# STM32F407_CORE.net
KiCad netlist of a schematic drawn in Altium Designer
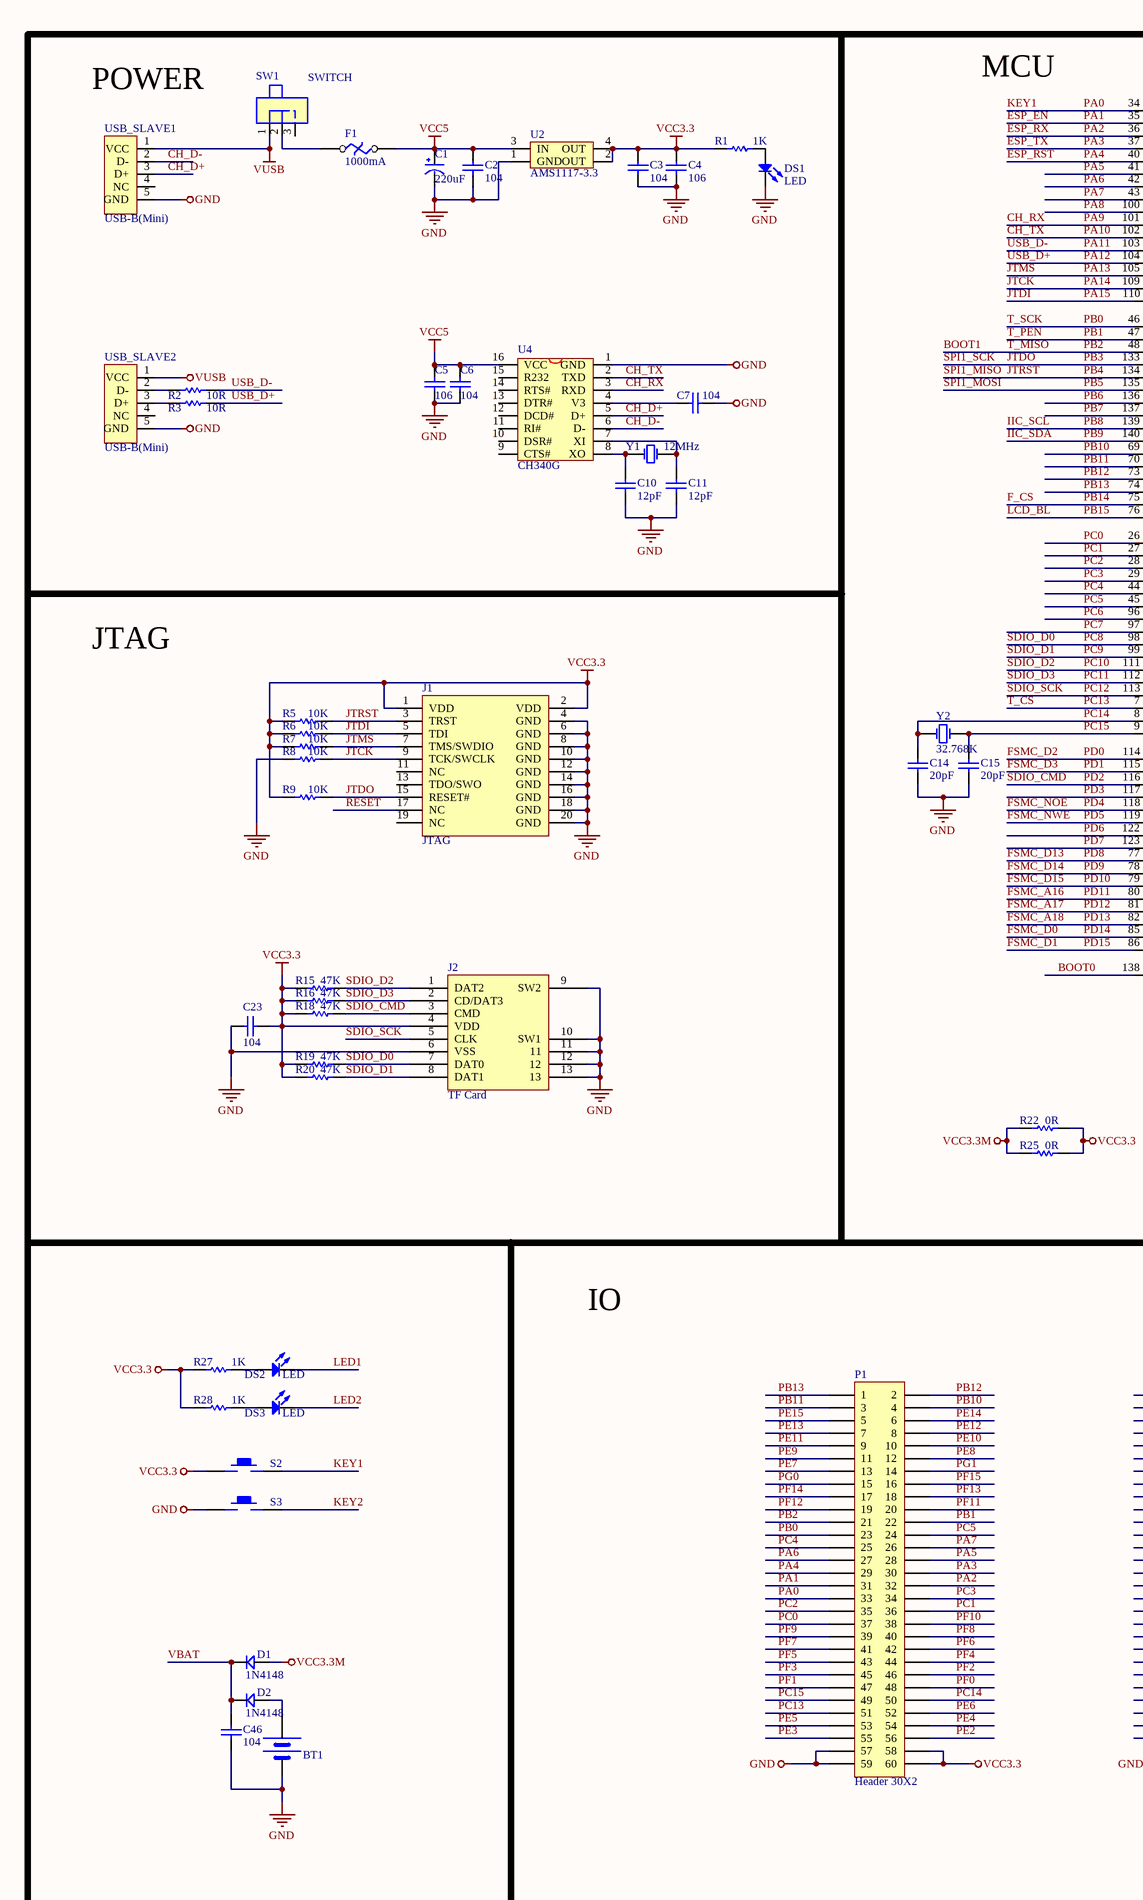
[diagram p0: STM32F407_CORE.SchDoc, left]
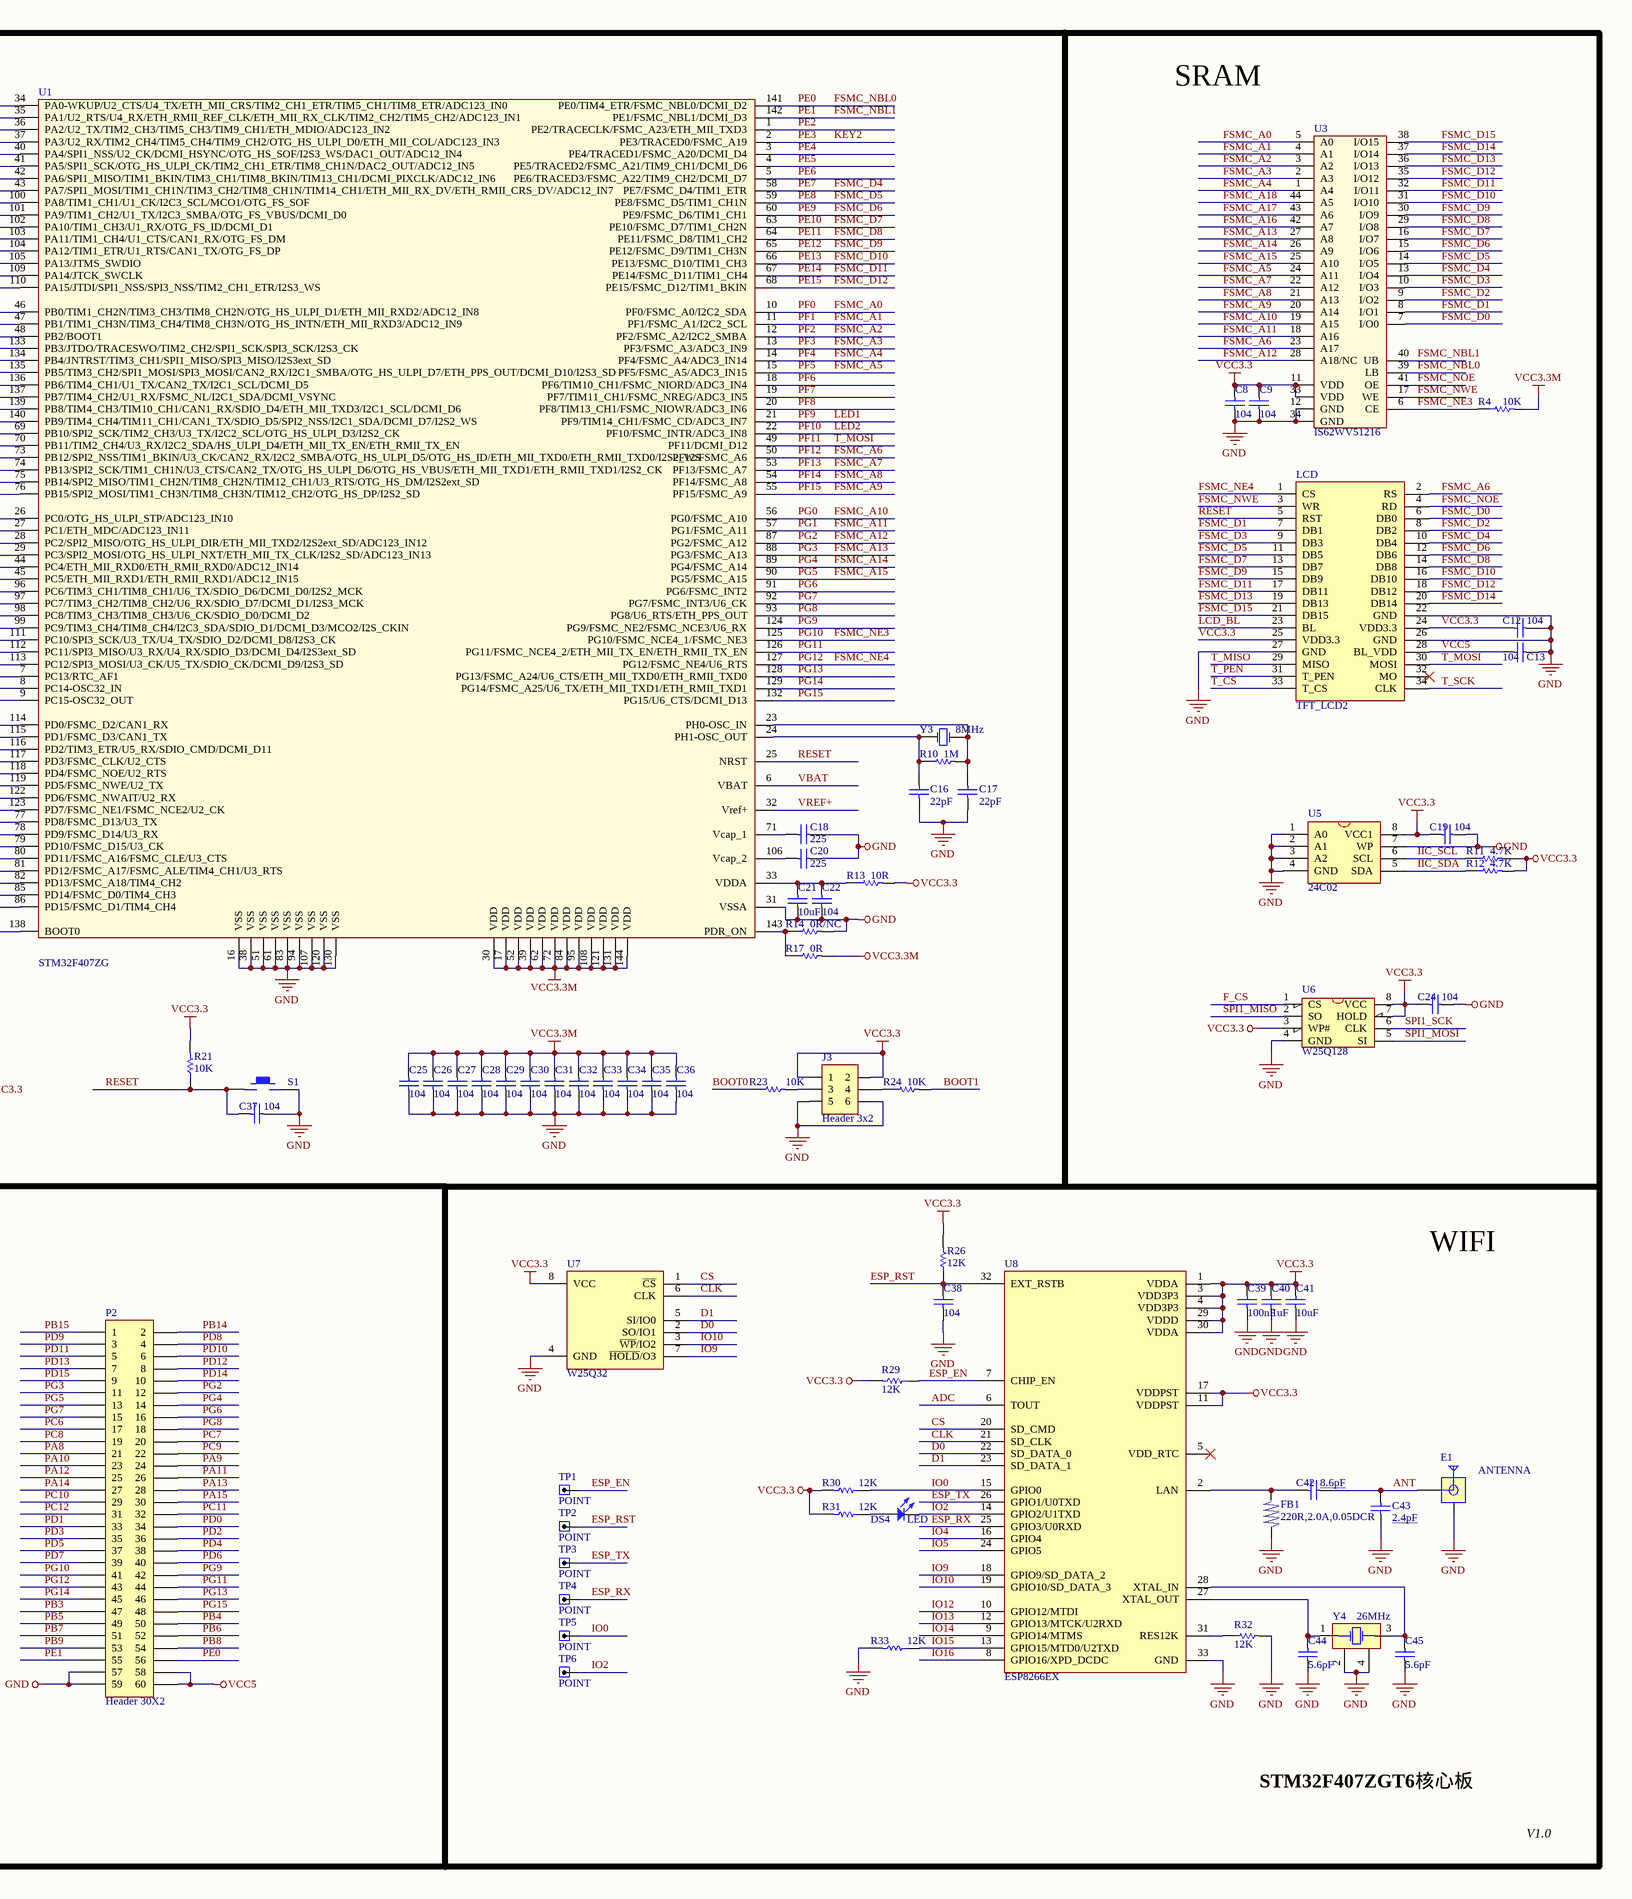
[diagram p1: STM32F407_CORE.SchDoc, right]

(export (version "E")
  (design (tool "Eeschema 10.0.6"))
  (components
    (comp (ref "BT1")
      (value "BATTERY")
      (footprint "SBAT-1220")
      (description "电池座")
      (libsource (lib "Devices") (part "BATTERY"))
    )
    (comp (ref "C1")
      (value "220uF")
      (footprint "TAJ-B")
      (description "极性电容")
      (libsource (lib "Devices") (part "C Pol"))
    )
    (comp (ref "C2")
      (value "104")
      (footprint "C0603")
      (description "电容")
      (fields (field (name "PUBLISHER") "Altium Limited"))
      (libsource (lib "Devices") (part "C"))
    )
    (comp (ref "C3")
      (value "104")
      (footprint "C0603")
      (description "电容")
      (fields (field (name "PUBLISHER") "Altium Limited"))
      (libsource (lib "Devices") (part "C"))
    )
    (comp (ref "C4")
      (value "106")
      (footprint "C0603")
      (description "电容")
      (fields (field (name "PUBLISHER") "Altium Limited"))
      (libsource (lib "Devices") (part "C"))
    )
    (comp (ref "C5")
      (value "106")
      (footprint "C0603")
      (description "电容")
      (fields (field (name "PUBLISHER") "Altium Limited"))
      (libsource (lib "Devices") (part "C"))
    )
    (comp (ref "C6")
      (value "104")
      (footprint "C0603")
      (description "电容")
      (fields (field (name "PUBLISHER") "Altium Limited"))
      (libsource (lib "Devices") (part "C"))
    )
    (comp (ref "C7")
      (value "104")
      (footprint "C0603")
      (description "电容")
      (fields (field (name "PUBLISHER") "Altium Limited"))
      (libsource (lib "Devices") (part "C"))
    )
    (comp (ref "C8")
      (value "104")
      (footprint "C0603")
      (description "电容")
      (fields (field (name "PUBLISHER") "Altium Limited"))
      (libsource (lib "Devices") (part "C"))
    )
    (comp (ref "C9")
      (value "104")
      (footprint "C0603")
      (description "电容")
      (fields (field (name "PUBLISHER") "Altium Limited"))
      (libsource (lib "Devices") (part "C"))
    )
    (comp (ref "C10")
      (value "12pF")
      (footprint "C0603")
      (description "电容")
      (fields (field (name "PUBLISHER") "Altium Limited"))
      (libsource (lib "Devices") (part "C"))
    )
    (comp (ref "C11")
      (value "12pF")
      (footprint "C0603")
      (description "电容")
      (fields (field (name "PUBLISHER") "Altium Limited"))
      (libsource (lib "Devices") (part "C"))
    )
    (comp (ref "C12")
      (value "104")
      (footprint "C0603")
      (description "电容")
      (fields (field (name "PUBLISHER") "Altium Limited"))
      (libsource (lib "Devices") (part "C"))
    )
    (comp (ref "C13")
      (value "104")
      (footprint "C0603")
      (description "电容")
      (fields (field (name "PUBLISHER") "Altium Limited"))
      (libsource (lib "Devices") (part "C"))
    )
    (comp (ref "C14")
      (value "20pF")
      (footprint "C0603")
      (description "电容")
      (fields (field (name "PUBLISHER") "Altium Limited"))
      (libsource (lib "Devices") (part "C"))
    )
    (comp (ref "C15")
      (value "20pF")
      (footprint "C0603")
      (description "电容")
      (fields (field (name "PUBLISHER") "Altium Limited"))
      (libsource (lib "Devices") (part "C"))
    )
    (comp (ref "C16")
      (value "22pF")
      (footprint "C0603")
      (description "电容")
      (fields (field (name "PUBLISHER") "Altium Limited"))
      (libsource (lib "Devices") (part "C"))
    )
    (comp (ref "C17")
      (value "22pF")
      (footprint "C0603")
      (description "电容")
      (fields (field (name "PUBLISHER") "Altium Limited"))
      (libsource (lib "Devices") (part "C"))
    )
    (comp (ref "C18")
      (value "225")
      (footprint "C0603")
      (description "电容")
      (fields (field (name "PUBLISHER") "Altium Limited"))
      (libsource (lib "Devices") (part "C"))
    )
    (comp (ref "C19")
      (value "104")
      (footprint "C0603")
      (description "电容")
      (fields (field (name "PUBLISHER") "Altium Limited"))
      (libsource (lib "Devices") (part "C"))
    )
    (comp (ref "C20")
      (value "225")
      (footprint "C0603")
      (description "电容")
      (fields (field (name "PUBLISHER") "Altium Limited"))
      (libsource (lib "Devices") (part "C"))
    )
    (comp (ref "C21")
      (value "10uF")
      (footprint "C0603")
      (description "电容")
      (fields (field (name "PUBLISHER") "Altium Limited"))
      (libsource (lib "Devices") (part "C"))
    )
    (comp (ref "C22")
      (value "104")
      (footprint "C0603")
      (description "电容")
      (fields (field (name "PUBLISHER") "Altium Limited"))
      (libsource (lib "Devices") (part "C"))
    )
    (comp (ref "C23")
      (value "104")
      (footprint "C0603")
      (description "电容")
      (fields (field (name "PUBLISHER") "Altium Limited"))
      (libsource (lib "Devices") (part "C"))
    )
    (comp (ref "C24")
      (value "104")
      (footprint "C0603")
      (description "电容")
      (fields (field (name "PUBLISHER") "Altium Limited"))
      (libsource (lib "Devices") (part "C"))
    )
    (comp (ref "C25")
      (value "104")
      (footprint "C0603")
      (description "电容")
      (fields (field (name "PUBLISHER") "Altium Limited"))
      (libsource (lib "Devices") (part "C"))
    )
    (comp (ref "C26")
      (value "104")
      (footprint "C0603")
      (description "电容")
      (fields (field (name "PUBLISHER") "Altium Limited"))
      (libsource (lib "Devices") (part "C"))
    )
    (comp (ref "C27")
      (value "104")
      (footprint "C0603")
      (description "电容")
      (fields (field (name "PUBLISHER") "Altium Limited"))
      (libsource (lib "Devices") (part "C"))
    )
    (comp (ref "C28")
      (value "104")
      (footprint "C0603")
      (description "电容")
      (fields (field (name "PUBLISHER") "Altium Limited"))
      (libsource (lib "Devices") (part "C"))
    )
    (comp (ref "C29")
      (value "104")
      (footprint "C0603")
      (description "电容")
      (fields (field (name "PUBLISHER") "Altium Limited"))
      (libsource (lib "Devices") (part "C"))
    )
    (comp (ref "C30")
      (value "104")
      (footprint "C0603")
      (description "电容")
      (fields (field (name "PUBLISHER") "Altium Limited"))
      (libsource (lib "Devices") (part "C"))
    )
    (comp (ref "C31")
      (value "104")
      (footprint "C0603")
      (description "电容")
      (fields (field (name "PUBLISHER") "Altium Limited"))
      (libsource (lib "Devices") (part "C"))
    )
    (comp (ref "C32")
      (value "104")
      (footprint "C0603")
      (description "电容")
      (fields (field (name "PUBLISHER") "Altium Limited"))
      (libsource (lib "Devices") (part "C"))
    )
    (comp (ref "C33")
      (value "104")
      (footprint "C0603")
      (description "电容")
      (fields (field (name "PUBLISHER") "Altium Limited"))
      (libsource (lib "Devices") (part "C"))
    )
    (comp (ref "C34")
      (value "104")
      (footprint "C0603")
      (description "电容")
      (fields (field (name "PUBLISHER") "Altium Limited"))
      (libsource (lib "Devices") (part "C"))
    )
    (comp (ref "C35")
      (value "104")
      (footprint "C0603")
      (description "电容")
      (fields (field (name "PUBLISHER") "Altium Limited"))
      (libsource (lib "Devices") (part "C"))
    )
    (comp (ref "C36")
      (value "104")
      (footprint "C0603")
      (description "电容")
      (fields (field (name "PUBLISHER") "Altium Limited"))
      (libsource (lib "Devices") (part "C"))
    )
    (comp (ref "C37")
      (value "104")
      (footprint "C0603")
      (description "电容")
      (fields (field (name "PUBLISHER") "Altium Limited"))
      (libsource (lib "Devices") (part "C"))
    )
    (comp (ref "C38")
      (value "104")
      (footprint "C0603")
      (description "电容")
      (fields (field (name "PUBLISHER") "Altium Limited"))
      (libsource (lib "Devices") (part "C"))
    )
    (comp (ref "C39")
      (value "100nF")
      (footprint "C0603")
      (description "电容")
      (fields (field (name "PUBLISHER") "Altium Limited"))
      (libsource (lib "Devices") (part "C"))
    )
    (comp (ref "C40")
      (value "1uF")
      (footprint "C0603")
      (description "电容")
      (fields (field (name "PUBLISHER") "Altium Limited"))
      (libsource (lib "Devices") (part "C"))
    )
    (comp (ref "C41")
      (value "10uF")
      (footprint "C0603")
      (description "电容")
      (fields (field (name "PUBLISHER") "Altium Limited"))
      (libsource (lib "Devices") (part "C"))
    )
    (comp (ref "C42")
      (value "8.6pF")
      (footprint "C0603")
      (description "电容")
      (fields (field (name "PUBLISHER") "Altium Limited"))
      (libsource (lib "Devices") (part "C"))
    )
    (comp (ref "C43")
      (value "2.4pF")
      (footprint "C0603")
      (description "电容")
      (fields (field (name "PUBLISHER") "Altium Limited"))
      (libsource (lib "Devices") (part "C"))
    )
    (comp (ref "C44")
      (value "5.6pF")
      (footprint "C0603")
      (description "电容")
      (fields (field (name "PUBLISHER") "Altium Limited"))
      (libsource (lib "Devices") (part "C"))
    )
    (comp (ref "C45")
      (value "5.6pF")
      (footprint "C0603")
      (description "电容")
      (fields (field (name "PUBLISHER") "Altium Limited"))
      (libsource (lib "Devices") (part "C"))
    )
    (comp (ref "C46")
      (value "104")
      (footprint "C0603")
      (description "电容")
      (fields (field (name "PUBLISHER") "Altium Limited"))
      (libsource (lib "Devices") (part "C"))
    )
    (comp (ref "D1")
      (value "1N4148")
      (footprint "D1206")
      (description "通用二极管")
      (libsource (lib "Devices") (part "D"))
    )
    (comp (ref "D2")
      (value "1N4148")
      (footprint "D1206")
      (description "通用二极管")
      (libsource (lib "Devices") (part "D"))
    )
    (comp (ref "DS1")
      (value "LED")
      (footprint "LED0603")
      (description "Typical RED, GREEN, YELLOW, AMBER GaAs LED")
      (fields (field (name "PUBLISHER") "Altium Limited"))
      (libsource (lib "Devices") (part "LED"))
    )
    (comp (ref "DS2")
      (value "LED")
      (footprint "LED0603")
      (description "Typical RED, GREEN, YELLOW, AMBER GaAs LED")
      (fields (field (name "PUBLISHER") "Altium Limited"))
      (libsource (lib "Devices") (part "LED"))
    )
    (comp (ref "DS3")
      (value "LED")
      (footprint "LED0603")
      (description "Typical RED, GREEN, YELLOW, AMBER GaAs LED")
      (fields (field (name "PUBLISHER") "Altium Limited"))
      (libsource (lib "Devices") (part "LED"))
    )
    (comp (ref "DS4")
      (value "LED")
      (footprint "LED0603")
      (description "Typical RED, GREEN, YELLOW, AMBER GaAs LED")
      (fields (field (name "PUBLISHER") "Altium Limited"))
      (libsource (lib "Devices") (part "LED"))
    )
    (comp (ref "E1") (value "ANTENNA") (footprint "ANT2.4G") (libsource (lib "Devices") (part "ANTENNA")))
    (comp (ref "F1")
      (value "1000mA")
      (footprint "F0805")
      (description "熔断开关")
      (libsource (lib "Devices") (part "F"))
    )
    (comp (ref "FB1")
      (value "220R,2.0A,0.05DCR")
      (footprint "L0805")
      (description "磁珠")
      (libsource (lib "Devices") (part "L-Beads"))
    )
    (comp (ref "J1") (value "JTAG") (footprint "DC3-20P-W") (libsource (lib "Connectors") (part "JTAG")))
    (comp (ref "J2") (value "TF Card") (footprint "TF-Card") (libsource (lib "Devices") (part "TF Card")))
    (comp (ref "J3")
      (value "Header 3x2")
      (footprint "HDR2X3")
      (description "Header, 6-Pin")
      (fields (field (name "PUBLISHER") "Altium Limited"))
      (libsource (lib "Connectors") (part "Header 3x2"))
    )
    (comp (ref "LCD")
      (value "TFT_LCD2")
      (footprint "TFT-HDR2X17")
      (libsource (lib "Connectors") (part "TFT_LCD2"))
    )
    (comp (ref "P1")
      (value "Header 30X2")
      (footprint "HDR2X30")
      (description "Header, 60-Pin, Dual row")
      (fields (field (name "PUBLISHER") "Altium Limited"))
      (libsource (lib "Connectors") (part "Header 30X2"))
    )
    (comp (ref "P2")
      (value "Header 30X2")
      (footprint "HDR2X30")
      (description "Header, 60-Pin, Dual row")
      (fields (field (name "PUBLISHER") "Altium Limited"))
      (libsource (lib "Connectors") (part "Header 30X2"))
    )
    (comp (ref "R1")
      (value "1K")
      (footprint "R0603")
      (description "电阻")
      (fields (field (name "PUBLISHER") "Altium Limited"))
      (libsource (lib "Devices") (part "RES0603"))
    )
    (comp (ref "R2")
      (value "10R")
      (footprint "R0603")
      (description "电阻")
      (fields (field (name "PUBLISHER") "Altium Limited"))
      (libsource (lib "Devices") (part "RES0603"))
    )
    (comp (ref "R3")
      (value "10R")
      (footprint "R0603")
      (description "电阻")
      (fields (field (name "PUBLISHER") "Altium Limited"))
      (libsource (lib "Devices") (part "RES0603"))
    )
    (comp (ref "R4")
      (value "10K")
      (footprint "R0603")
      (description "电阻")
      (fields (field (name "PUBLISHER") "Altium Limited"))
      (libsource (lib "Devices") (part "RES0603"))
    )
    (comp (ref "R5")
      (value "10K")
      (footprint "R0603")
      (description "电阻")
      (fields (field (name "PUBLISHER") "Altium Limited"))
      (libsource (lib "Devices") (part "RES0603"))
    )
    (comp (ref "R6")
      (value "10K")
      (footprint "R0603")
      (description "电阻")
      (fields (field (name "PUBLISHER") "Altium Limited"))
      (libsource (lib "Devices") (part "RES0603"))
    )
    (comp (ref "R7")
      (value "10K")
      (footprint "R0603")
      (description "电阻")
      (fields (field (name "PUBLISHER") "Altium Limited"))
      (libsource (lib "Devices") (part "RES0603"))
    )
    (comp (ref "R8")
      (value "10K")
      (footprint "R0603")
      (description "电阻")
      (fields (field (name "PUBLISHER") "Altium Limited"))
      (libsource (lib "Devices") (part "RES0603"))
    )
    (comp (ref "R9")
      (value "10K")
      (footprint "R0603")
      (description "电阻")
      (fields (field (name "PUBLISHER") "Altium Limited"))
      (libsource (lib "Devices") (part "RES0603"))
    )
    (comp (ref "R10")
      (value "1M")
      (footprint "R0603")
      (description "电阻")
      (fields (field (name "PUBLISHER") "Altium Limited"))
      (libsource (lib "Devices") (part "RES0603"))
    )
    (comp (ref "R11")
      (value "4.7K")
      (footprint "R0603")
      (description "电阻")
      (fields (field (name "PUBLISHER") "Altium Limited"))
      (libsource (lib "Devices") (part "RES0603"))
    )
    (comp (ref "R12")
      (value "4.7K")
      (footprint "R0603")
      (description "电阻")
      (fields (field (name "PUBLISHER") "Altium Limited"))
      (libsource (lib "Devices") (part "RES0603"))
    )
    (comp (ref "R13")
      (value "10R")
      (footprint "R0603")
      (description "电阻")
      (fields (field (name "PUBLISHER") "Altium Limited"))
      (libsource (lib "Devices") (part "RES0603"))
    )
    (comp (ref "R14")
      (value "0R/NC")
      (footprint "R0603")
      (description "电阻")
      (fields (field (name "PUBLISHER") "Altium Limited"))
      (libsource (lib "Devices") (part "RES0603"))
    )
    (comp (ref "R15")
      (value "47K")
      (footprint "R0603")
      (description "电阻")
      (fields (field (name "PUBLISHER") "Altium Limited"))
      (libsource (lib "Devices") (part "RES0603"))
    )
    (comp (ref "R16")
      (value "47K")
      (footprint "R0603")
      (description "电阻")
      (fields (field (name "PUBLISHER") "Altium Limited"))
      (libsource (lib "Devices") (part "RES0603"))
    )
    (comp (ref "R17")
      (value "0R")
      (footprint "R0603")
      (description "电阻")
      (fields (field (name "PUBLISHER") "Altium Limited"))
      (libsource (lib "Devices") (part "RES0603"))
    )
    (comp (ref "R18")
      (value "47K")
      (footprint "R0603")
      (description "电阻")
      (fields (field (name "PUBLISHER") "Altium Limited"))
      (libsource (lib "Devices") (part "RES0603"))
    )
    (comp (ref "R19")
      (value "47K")
      (footprint "R0603")
      (description "电阻")
      (fields (field (name "PUBLISHER") "Altium Limited"))
      (libsource (lib "Devices") (part "RES0603"))
    )
    (comp (ref "R20")
      (value "47K")
      (footprint "R0603")
      (description "电阻")
      (fields (field (name "PUBLISHER") "Altium Limited"))
      (libsource (lib "Devices") (part "RES0603"))
    )
    (comp (ref "R21")
      (value "10K")
      (footprint "R0603")
      (description "电阻")
      (fields (field (name "PUBLISHER") "Altium Limited"))
      (libsource (lib "Devices") (part "RES0603"))
    )
    (comp (ref "R22")
      (value "0R")
      (footprint "R0603")
      (description "电阻")
      (fields (field (name "PUBLISHER") "Altium Limited"))
      (libsource (lib "Devices") (part "RES0603"))
    )
    (comp (ref "R23")
      (value "10K")
      (footprint "R0603")
      (description "电阻")
      (fields (field (name "PUBLISHER") "Altium Limited"))
      (libsource (lib "Devices") (part "RES0603"))
    )
    (comp (ref "R24")
      (value "10K")
      (footprint "R0603")
      (description "电阻")
      (fields (field (name "PUBLISHER") "Altium Limited"))
      (libsource (lib "Devices") (part "RES0603"))
    )
    (comp (ref "R25")
      (value "0R")
      (footprint "R0603")
      (description "电阻")
      (fields (field (name "PUBLISHER") "Altium Limited"))
      (libsource (lib "Devices") (part "RES0603"))
    )
    (comp (ref "R26")
      (value "12K")
      (footprint "R0603")
      (description "电阻")
      (fields (field (name "PUBLISHER") "Altium Limited"))
      (libsource (lib "Devices") (part "RES0603"))
    )
    (comp (ref "R27")
      (value "1K")
      (footprint "R0603")
      (description "电阻")
      (fields (field (name "PUBLISHER") "Altium Limited"))
      (libsource (lib "Devices") (part "RES0603"))
    )
    (comp (ref "R28")
      (value "1K")
      (footprint "R0603")
      (description "电阻")
      (fields (field (name "PUBLISHER") "Altium Limited"))
      (libsource (lib "Devices") (part "RES0603"))
    )
    (comp (ref "R29")
      (value "12K")
      (footprint "R0603")
      (description "电阻")
      (fields (field (name "PUBLISHER") "Altium Limited"))
      (libsource (lib "Devices") (part "RES0603"))
    )
    (comp (ref "R30")
      (value "12K")
      (footprint "R0603")
      (description "电阻")
      (fields (field (name "PUBLISHER") "Altium Limited"))
      (libsource (lib "Devices") (part "RES0603"))
    )
    (comp (ref "R31")
      (value "12K")
      (footprint "R0603")
      (description "电阻")
      (fields (field (name "PUBLISHER") "Altium Limited"))
      (libsource (lib "Devices") (part "RES0603"))
    )
    (comp (ref "R32")
      (value "12K")
      (footprint "R0603")
      (description "电阻")
      (fields (field (name "PUBLISHER") "Altium Limited"))
      (libsource (lib "Devices") (part "RES0603"))
    )
    (comp (ref "R33")
      (value "12K")
      (footprint "R0603")
      (description "电阻")
      (fields (field (name "PUBLISHER") "Altium Limited"))
      (libsource (lib "Devices") (part "RES0603"))
    )
    (comp (ref "S1")
      (value "KEY")
      (footprint "DSW-KFC-022S-H2.5")
      (description "普通轻触按钮")
      (libsource (lib "Devices") (part "KEY"))
    )
    (comp (ref "S2")
      (value "KEY")
      (footprint "DSW-KEY-SOT-4_5x4_5")
      (description "普通轻触按钮")
      (libsource (lib "Devices") (part "KEY"))
    )
    (comp (ref "S3")
      (value "KEY")
      (footprint "DSW-KEY-SOT-4_5x4_5")
      (description "普通轻触按钮")
      (libsource (lib "Devices") (part "KEY"))
    )
    (comp (ref "SW1")
      (value "SWITCH")
      (footprint "SW-SS12D07VG4")
      (libsource (lib "Devices") (part "SWITCH"))
    )
    (comp (ref "TP1") (value "POINT") (footprint "TP12") (libsource (lib "Connectors") (part "POINT")))
    (comp (ref "TP2") (value "POINT") (footprint "TP12") (libsource (lib "Connectors") (part "POINT")))
    (comp (ref "TP3") (value "POINT") (footprint "TP12") (libsource (lib "Connectors") (part "POINT")))
    (comp (ref "TP4") (value "POINT") (footprint "TP12") (libsource (lib "Connectors") (part "POINT")))
    (comp (ref "TP5") (value "POINT") (footprint "TP12") (libsource (lib "Connectors") (part "POINT")))
    (comp (ref "TP6") (value "POINT") (footprint "TP12") (libsource (lib "Connectors") (part "POINT")))
    (comp (ref "U1") (value "STM32F407ZG") (footprint "LQFP-144") (libsource (lib "IC") (part "STM32F407ZG")))
    (comp (ref "U2")
      (value "AMS1117-3.3")
      (footprint "SOT-223")
      (description "电源转换5Vto3.3V")
      (libsource (lib "IC") (part "AMS1117"))
    )
    (comp (ref "U3") (value "IS62WV51216") (footprint "TSOP-44") (libsource (lib "IC") (part "IS61LV51216")))
    (comp (ref "U4")
      (value "CH340G")
      (footprint "SOP-16M")
      (description "USB2UART")
      (libsource (lib "IC") (part "CH340G"))
    )
    (comp (ref "U5") (value "24C02") (footprint "SOP-8") (libsource (lib "IC") (part "24C256")))
    (comp (ref "U6")
      (value "W25Q128")
      (footprint "SOIC-8")
      (description "W25X16;SST25VF016;MX25L1605")
      (libsource (lib "IC") (part "W25X16"))
    )
    (comp (ref "U7") (value "W25Q32") (footprint "SOIC-8") (libsource (lib "IC") (part "W25Q32")))
    (comp (ref "U8") (value "ESP8266EX") (footprint "QFN-32-1") (libsource (lib "IC") (part "ESP8266EX")))
    (comp (ref "USB_SLAVE1")
      (value "USB-B(Mini)")
      (footprint "USB-MicroUSB")
      (libsource (lib "Connectors") (part "USB5"))
    )
    (comp (ref "USB_SLAVE2")
      (value "USB-B(Mini)")
      (footprint "USB-MicroUSB")
      (libsource (lib "Connectors") (part "USB5"))
    )
    (comp (ref "Y1")
      (value "12MHz")
      (footprint "X-HC49-SMT")
      (description "Crystal Oscillator")
      (fields (field (name "PUBLISHER") "Altium Limited"))
      (libsource (lib "Devices") (part "XTAL"))
    )
    (comp (ref "Y2")
      (value "32.768K")
      (footprint "X-MC146")
      (description "Crystal Oscillator")
      (fields (field (name "PUBLISHER") "Altium Limited"))
      (libsource (lib "Devices") (part "XTAL"))
    )
    (comp (ref "Y3")
      (value "8MHz")
      (footprint "X-HC49-SMT")
      (description "Crystal Oscillator")
      (fields (field (name "PUBLISHER") "Altium Limited"))
      (libsource (lib "Devices") (part "XTAL"))
    )
    (comp (ref "Y4")
      (value "26MHz")
      (footprint "X-TSX-3225")
      (description "Crystal Oscillator")
      (fields (field (name "PUBLISHER") "Altium Limited"))
      (libsource (lib "Devices") (part "XTAL_1"))
    )
  )
  (nets
    (net (code "1") (name "/ADC") (class "Default")
      (node (ref "U8") (pin "6") (pinfunction "TOUT_6") (pintype "power_in"))
    )
    (net (code "2") (name "/ANT") (class "Default")
      (node (ref "C42") (pin "1") (pinfunction "1_1") (pintype "passive"))
      (node (ref "C43") (pin "1") (pinfunction "1_1") (pintype "passive"))
      (node (ref "E1") (pin "1") (pinfunction "1_1") (pintype "passive"))
    )
    (net (code "3") (name "/BOOT0") (class "Default")
      (node (ref "R23") (pin "1") (pinfunction "1_1") (pintype "passive"))
      (node (ref "U1") (pin "138") (pinfunction "BOOT0_138") (pintype "passive"))
    )
    (net (code "4") (name "/BOOT1") (class "Default")
      (node (ref "LCD") (pin "29") (pinfunction "MISO_29") (pintype "passive"))
      (node (ref "P1") (pin "21") (pinfunction "21_21") (pintype "passive"))
      (node (ref "R24") (pin "2") (pinfunction "2_2") (pintype "passive"))
      (node (ref "U1") (pin "48") (pinfunction "PB2/BOOT1_48") (pintype "passive"))
    )
    (net (code "5") (name "/CH_D+") (class "Default")
      (node (ref "U4") (pin "5") (pinfunction "D+_5") (pintype "passive"))
      (node (ref "USB_SLAVE1") (pin "3") (pinfunction "D+_3") (pintype "passive"))
    )
    (net (code "6") (name "/CH_D-") (class "Default")
      (node (ref "U4") (pin "6") (pinfunction "D-_6") (pintype "passive"))
      (node (ref "USB_SLAVE1") (pin "2") (pinfunction "D-_2") (pintype "passive"))
    )
    (net (code "7") (name "/CH_RX") (class "Default")
      (node (ref "P2") (pin "24") (pinfunction "24_24") (pintype "passive"))
      (node (ref "U1") (pin "101") (pinfunction "PA9/TIM1_CH2/U1_TX/I2C3_SMBA/OTG_FS_VBUS/DCMI_D0_101") (pintype "passive"))
      (node (ref "U4") (pin "3") (pinfunction "RXD_3") (pintype "passive"))
    )
    (net (code "8") (name "/CH_TX") (class "Default")
      (node (ref "P2") (pin "23") (pinfunction "23_23") (pintype "passive"))
      (node (ref "U1") (pin "102") (pinfunction "PA10/TIM1_CH3/U1_RX/OTG_FS_ID/DCMI_D1_102") (pintype "passive"))
      (node (ref "U4") (pin "2") (pinfunction "TXD_2") (pintype "passive"))
    )
    (net (code "9") (name "/CLK") (class "Default")
      (node (ref "U7") (pin "6") (pinfunction "CLK_6") (pintype "power_in"))
      (node (ref "U8") (pin "21") (pinfunction "SD_CLK_21") (pintype "power_in"))
    )
    (net (code "10") (name "/CS") (class "Default")
      (node (ref "U7") (pin "1") (pinfunction "~{CS}_1") (pintype "power_in"))
      (node (ref "U8") (pin "20") (pinfunction "SD_CMD_20") (pintype "power_in"))
    )
    (net (code "11") (name "/D0") (class "Default")
      (node (ref "U7") (pin "2") (pinfunction "SO/IO1_2") (pintype "power_in"))
      (node (ref "U8") (pin "22") (pinfunction "SD_DATA_0_22") (pintype "power_in"))
    )
    (net (code "12") (name "/D1") (class "Default")
      (node (ref "U7") (pin "5") (pinfunction "SI/IO0_5") (pintype "power_in"))
      (node (ref "U8") (pin "23") (pinfunction "SD_DATA_1_23") (pintype "power_in"))
    )
    (net (code "13") (name "/ESP_EN") (class "Default")
      (node (ref "P1") (pin "31") (pinfunction "31_31") (pintype "passive"))
      (node (ref "R29") (pin "1") (pinfunction "1_1") (pintype "passive"))
      (node (ref "TP1") (pin "1") (pinfunction "1_1") (pintype "passive"))
      (node (ref "U1") (pin "35") (pinfunction "PA1/U2_RTS/U4_RX/ETH_RMII_REF_CLK/ETH_MII_RX_CLK/TIM2_CH2/TIM5_CH2/ADC123_IN1_35") (pintype "passive"))
      (node (ref "U8") (pin "7") (pinfunction "CHIP_EN_7") (pintype "power_in"))
    )
    (net (code "14") (name "/ESP_RST") (class "Default")
      (node (ref "C38") (pin "2") (pinfunction "2_2") (pintype "passive"))
      (node (ref "P1") (pin "29") (pinfunction "29_29") (pintype "passive"))
      (node (ref "R26") (pin "1") (pinfunction "1_1") (pintype "passive"))
      (node (ref "TP2") (pin "1") (pinfunction "1_1") (pintype "passive"))
      (node (ref "U1") (pin "40") (pinfunction "PA4/SPI1_NSS/U2_CK/DCMI_HSYNC/OTG_HS_SOF/I2S3_WS/DAC1_OUT/ADC12_IN4_40") (pintype "passive"))
      (node (ref "U8") (pin "32") (pinfunction "EXT_RSTB_32") (pintype "power_in"))
    )
    (net (code "15") (name "/ESP_RX") (class "Default")
      (node (ref "P1") (pin "32") (pinfunction "32_32") (pintype "passive"))
      (node (ref "TP4") (pin "1") (pinfunction "1_1") (pintype "passive"))
      (node (ref "U1") (pin "36") (pinfunction "PA2/U2_TX/TIM2_CH3/TIM5_CH3/TIM9_CH1/ETH_MDIO/ADC123_IN2_36") (pintype "passive"))
      (node (ref "U8") (pin "25") (pinfunction "GPIO3/U0RXD_25") (pintype "power_in"))
    )
    (net (code "16") (name "/ESP_TX") (class "Default")
      (node (ref "P1") (pin "30") (pinfunction "30_30") (pintype "passive"))
      (node (ref "TP3") (pin "1") (pinfunction "1_1") (pintype "passive"))
      (node (ref "U1") (pin "37") (pinfunction "PA3/U2_RX/TIM2_CH4/TIM5_CH4/TIM9_CH2/OTG_HS_ULPI_D0/ETH_MII_COL/ADC123_IN3_37") (pintype "passive"))
      (node (ref "U8") (pin "26") (pinfunction "GPIO1/U0TXD_26") (pintype "power_in"))
    )
    (net (code "17") (name "/FSMC_A0") (class "Default")
      (node (ref "P1") (pin "48") (pinfunction "48_48") (pintype "passive"))
      (node (ref "U1") (pin "10") (pinfunction "PF0/FSMC_A0/I2C2_SDA_10") (pintype "passive"))
      (node (ref "U3") (pin "5") (pinfunction "A0_5") (pintype "passive"))
    )
    (net (code "18") (name "/FSMC_A1") (class "Default")
      (node (ref "P1") (pin "47") (pinfunction "47_47") (pintype "passive"))
      (node (ref "U1") (pin "11") (pinfunction "PF1/FSMC_A1/I2C2_SCL_11") (pintype "passive"))
      (node (ref "U3") (pin "4") (pinfunction "A1_4") (pintype "passive"))
    )
    (net (code "19") (name "/FSMC_A2") (class "Default")
      (node (ref "P1") (pin "46") (pinfunction "46_46") (pintype "passive"))
      (node (ref "U1") (pin "12") (pinfunction "PF2/FSMC_A2/I2C2_SMBA_12") (pintype "passive"))
      (node (ref "U3") (pin "3") (pinfunction "A2_3") (pintype "passive"))
    )
    (net (code "20") (name "/FSMC_A3") (class "Default")
      (node (ref "P1") (pin "45") (pinfunction "45_45") (pintype "passive"))
      (node (ref "U1") (pin "13") (pinfunction "PF3/FSMC_A3/ADC3_IN9_13") (pintype "passive"))
      (node (ref "U3") (pin "2") (pinfunction "A3_2") (pintype "passive"))
    )
    (net (code "21") (name "/FSMC_A4") (class "Default")
      (node (ref "P1") (pin "44") (pinfunction "44_44") (pintype "passive"))
      (node (ref "U1") (pin "14") (pinfunction "PF4/FSMC_A4/ADC3_IN14_14") (pintype "passive"))
      (node (ref "U3") (pin "1") (pinfunction "A4_1") (pintype "passive"))
    )
    (net (code "22") (name "/FSMC_A5") (class "Default")
      (node (ref "P1") (pin "43") (pinfunction "43_43") (pintype "passive"))
      (node (ref "U1") (pin "15") (pinfunction "PF5/FSMC_A5/ADC3_IN15_15") (pintype "passive"))
      (node (ref "U3") (pin "24") (pinfunction "A11_24") (pintype "passive"))
    )
    (net (code "23") (name "/FSMC_A6") (class "Default")
      (node (ref "LCD") (pin "2") (pinfunction "RS_2") (pintype "passive"))
      (node (ref "P1") (pin "19") (pinfunction "19_19") (pintype "passive"))
      (node (ref "U1") (pin "50") (pinfunction "PF12/FSMC_A6_50") (pintype "passive"))
      (node (ref "U3") (pin "23") (pinfunction "A17_23") (pintype "passive"))
    )
    (net (code "24") (name "/FSMC_A7") (class "Default")
      (node (ref "P1") (pin "18") (pinfunction "18_18") (pintype "passive"))
      (node (ref "U1") (pin "53") (pinfunction "PF13/FSMC_A7_53") (pintype "passive"))
      (node (ref "U3") (pin "22") (pinfunction "A12_22") (pintype "passive"))
    )
    (net (code "25") (name "/FSMC_A8") (class "Default")
      (node (ref "P1") (pin "17") (pinfunction "17_17") (pintype "passive"))
      (node (ref "U1") (pin "54") (pinfunction "PF14/FSMC_A8_54") (pintype "passive"))
      (node (ref "U3") (pin "21") (pinfunction "A13_21") (pintype "passive"))
    )
    (net (code "26") (name "/FSMC_A9") (class "Default")
      (node (ref "P1") (pin "16") (pinfunction "16_16") (pintype "passive"))
      (node (ref "U1") (pin "55") (pinfunction "PF15/FSMC_A9_55") (pintype "passive"))
      (node (ref "U3") (pin "20") (pinfunction "A14_20") (pintype "passive"))
    )
    (net (code "27") (name "/FSMC_A10") (class "Default")
      (node (ref "P1") (pin "15") (pinfunction "15_15") (pintype "passive"))
      (node (ref "U1") (pin "56") (pinfunction "PG0/FSMC_A10_56") (pintype "passive"))
      (node (ref "U3") (pin "19") (pinfunction "A15_19") (pintype "passive"))
    )
    (net (code "28") (name "/FSMC_A11") (class "Default")
      (node (ref "P1") (pin "14") (pinfunction "14_14") (pintype "passive"))
      (node (ref "U1") (pin "57") (pinfunction "PG1/FSMC_A11_57") (pintype "passive"))
      (node (ref "U3") (pin "18") (pinfunction "A16_18") (pintype "passive"))
    )
    (net (code "29") (name "/FSMC_A12") (class "Default")
      (node (ref "P2") (pin "12") (pinfunction "12_12") (pintype "passive"))
      (node (ref "U1") (pin "87") (pinfunction "PG2/FSMC_A12_87") (pintype "passive"))
      (node (ref "U3") (pin "28") (pinfunction "A18/NC_28") (pintype "passive"))
    )
    (net (code "30") (name "/FSMC_A13") (class "Default")
      (node (ref "P2") (pin "11") (pinfunction "11_11") (pintype "passive"))
      (node (ref "U1") (pin "88") (pinfunction "PG3/FSMC_A13_88") (pintype "passive"))
      (node (ref "U3") (pin "27") (pinfunction "A8_27") (pintype "passive"))
    )
    (net (code "31") (name "/FSMC_A14") (class "Default")
      (node (ref "P2") (pin "14") (pinfunction "14_14") (pintype "passive"))
      (node (ref "U1") (pin "89") (pinfunction "PG4/FSMC_A14_89") (pintype "passive"))
      (node (ref "U3") (pin "26") (pinfunction "A9_26") (pintype "passive"))
    )
    (net (code "32") (name "/FSMC_A15") (class "Default")
      (node (ref "P2") (pin "13") (pinfunction "13_13") (pintype "passive"))
      (node (ref "U1") (pin "90") (pinfunction "PG5/FSMC_A15_90") (pintype "passive"))
      (node (ref "U3") (pin "25") (pinfunction "A10_25") (pintype "passive"))
    )
    (net (code "33") (name "/FSMC_A16") (class "Default")
      (node (ref "P2") (pin "5") (pinfunction "5_5") (pintype "passive"))
      (node (ref "U1") (pin "80") (pinfunction "PD11/FSMC_A16/FSMC_CLE/U3_CTS_80") (pintype "passive"))
      (node (ref "U3") (pin "42") (pinfunction "A7_42") (pintype "passive"))
    )
    (net (code "34") (name "/FSMC_A17") (class "Default")
      (node (ref "P2") (pin "8") (pinfunction "8_8") (pintype "passive"))
      (node (ref "U1") (pin "81") (pinfunction "PD12/FSMC_A17/FSMC_ALE/TIM4_CH1/U3_RTS_81") (pintype "passive"))
      (node (ref "U3") (pin "43") (pinfunction "A6_43") (pintype "passive"))
    )
    (net (code "35") (name "/FSMC_A18") (class "Default")
      (node (ref "P2") (pin "7") (pinfunction "7_7") (pintype "passive"))
      (node (ref "U1") (pin "82") (pinfunction "PD13/FSMC_A18/TIM4_CH2_82") (pintype "passive"))
      (node (ref "U3") (pin "44") (pinfunction "A5_44") (pintype "passive"))
    )
    (net (code "36") (name "/FSMC_D0") (class "Default")
      (node (ref "LCD") (pin "6") (pinfunction "DB0_6") (pintype "passive"))
      (node (ref "P2") (pin "10") (pinfunction "10_10") (pintype "passive"))
      (node (ref "U1") (pin "85") (pinfunction "PD14/FSMC_D0/TIM4_CH3_85") (pintype "passive"))
      (node (ref "U3") (pin "7") (pinfunction "I/O0_7") (pintype "passive"))
    )
    (net (code "37") (name "/FSMC_D1") (class "Default")
      (node (ref "LCD") (pin "7") (pinfunction "DB1_7") (pintype "passive"))
      (node (ref "P2") (pin "9") (pinfunction "9_9") (pintype "passive"))
      (node (ref "U1") (pin "86") (pinfunction "PD15/FSMC_D1/TIM4_CH4_86") (pintype "passive"))
      (node (ref "U3") (pin "8") (pinfunction "I/O1_8") (pintype "passive"))
    )
    (net (code "38") (name "/FSMC_D2") (class "Default")
      (node (ref "LCD") (pin "8") (pinfunction "DB2_8") (pintype "passive"))
      (node (ref "P2") (pin "34") (pinfunction "34_34") (pintype "passive"))
      (node (ref "U1") (pin "114") (pinfunction "PD0/FSMC_D2/CAN1_RX_114") (pintype "passive"))
      (node (ref "U3") (pin "9") (pinfunction "I/O2_9") (pintype "passive"))
    )
    (net (code "39") (name "/FSMC_D3") (class "Default")
      (node (ref "LCD") (pin "9") (pinfunction "DB3_9") (pintype "passive"))
      (node (ref "P2") (pin "33") (pinfunction "33_33") (pintype "passive"))
      (node (ref "U1") (pin "115") (pinfunction "PD1/FSMC_D3/CAN1_TX_115") (pintype "passive"))
      (node (ref "U3") (pin "10") (pinfunction "I/O3_10") (pintype "passive"))
    )
    (net (code "40") (name "/FSMC_D4") (class "Default")
      (node (ref "LCD") (pin "10") (pinfunction "DB4_10") (pintype "passive"))
      (node (ref "P1") (pin "13") (pinfunction "13_13") (pintype "passive"))
      (node (ref "U1") (pin "58") (pinfunction "PE7/FSMC_D4/TIM1_ETR_58") (pintype "passive"))
      (node (ref "U3") (pin "13") (pinfunction "I/O4_13") (pintype "passive"))
    )
    (net (code "41") (name "/FSMC_D5") (class "Default")
      (node (ref "LCD") (pin "11") (pinfunction "DB5_11") (pintype "passive"))
      (node (ref "P1") (pin "12") (pinfunction "12_12") (pintype "passive"))
      (node (ref "U1") (pin "59") (pinfunction "PE8/FSMC_D5/TIM1_CH1N_59") (pintype "passive"))
      (node (ref "U3") (pin "14") (pinfunction "I/O5_14") (pintype "passive"))
    )
    (net (code "42") (name "/FSMC_D6") (class "Default")
      (node (ref "LCD") (pin "12") (pinfunction "DB6_12") (pintype "passive"))
      (node (ref "P1") (pin "11") (pinfunction "11_11") (pintype "passive"))
      (node (ref "U1") (pin "60") (pinfunction "PE9/FSMC_D6/TIM1_CH1_60") (pintype "passive"))
      (node (ref "U3") (pin "15") (pinfunction "I/O6_15") (pintype "passive"))
    )
    (net (code "43") (name "/FSMC_D7") (class "Default")
      (node (ref "LCD") (pin "13") (pinfunction "DB7_13") (pintype "passive"))
      (node (ref "P1") (pin "10") (pinfunction "10_10") (pintype "passive"))
      (node (ref "U1") (pin "63") (pinfunction "PE10/FSMC_D7/TIM1_CH2N_63") (pintype "passive"))
      (node (ref "U3") (pin "16") (pinfunction "I/O7_16") (pintype "passive"))
    )
    (net (code "44") (name "/FSMC_D8") (class "Default")
      (node (ref "LCD") (pin "14") (pinfunction "DB8_14") (pintype "passive"))
      (node (ref "P1") (pin "9") (pinfunction "9_9") (pintype "passive"))
      (node (ref "U1") (pin "64") (pinfunction "PE11/FSMC_D8/TIM1_CH2_64") (pintype "passive"))
      (node (ref "U3") (pin "29") (pinfunction "I/O8_29") (pintype "passive"))
    )
    (net (code "45") (name "/FSMC_D9") (class "Default")
      (node (ref "LCD") (pin "15") (pinfunction "DB9_15") (pintype "passive"))
      (node (ref "P1") (pin "8") (pinfunction "8_8") (pintype "passive"))
      (node (ref "U1") (pin "65") (pinfunction "PE12/FSMC_D9/TIM1_CH3N_65") (pintype "passive"))
      (node (ref "U3") (pin "30") (pinfunction "I/O9_30") (pintype "passive"))
    )
    (net (code "46") (name "/FSMC_D10") (class "Default")
      (node (ref "LCD") (pin "16") (pinfunction "DB10_16") (pintype "passive"))
      (node (ref "P1") (pin "7") (pinfunction "7_7") (pintype "passive"))
      (node (ref "U1") (pin "66") (pinfunction "PE13/FSMC_D10/TIM1_CH3_66") (pintype "passive"))
      (node (ref "U3") (pin "31") (pinfunction "I/O10_31") (pintype "passive"))
    )
    (net (code "47") (name "/FSMC_D11") (class "Default")
      (node (ref "LCD") (pin "17") (pinfunction "DB11_17") (pintype "passive"))
      (node (ref "P1") (pin "6") (pinfunction "6_6") (pintype "passive"))
      (node (ref "U1") (pin "67") (pinfunction "PE14/FSMC_D11/TIM1_CH4_67") (pintype "passive"))
      (node (ref "U3") (pin "32") (pinfunction "I/O11_32") (pintype "passive"))
    )
    (net (code "48") (name "/FSMC_D12") (class "Default")
      (node (ref "LCD") (pin "18") (pinfunction "DB12_18") (pintype "passive"))
      (node (ref "P1") (pin "5") (pinfunction "5_5") (pintype "passive"))
      (node (ref "U1") (pin "68") (pinfunction "PE15/FSMC_D12/TIM1_BKIN_68") (pintype "passive"))
      (node (ref "U3") (pin "35") (pinfunction "I/O12_35") (pintype "passive"))
    )
    (net (code "49") (name "/FSMC_D13") (class "Default")
      (node (ref "LCD") (pin "19") (pinfunction "DB13_19") (pintype "passive"))
      (node (ref "P2") (pin "4") (pinfunction "4_4") (pintype "passive"))
      (node (ref "U1") (pin "77") (pinfunction "PD8/FSMC_D13/U3_TX_77") (pintype "passive"))
      (node (ref "U3") (pin "36") (pinfunction "I/O13_36") (pintype "passive"))
    )
    (net (code "50") (name "/FSMC_D14") (class "Default")
      (node (ref "LCD") (pin "20") (pinfunction "DB14_20") (pintype "passive"))
      (node (ref "P2") (pin "3") (pinfunction "3_3") (pintype "passive"))
      (node (ref "U1") (pin "78") (pinfunction "PD9/FSMC_D14/U3_RX_78") (pintype "passive"))
      (node (ref "U3") (pin "37") (pinfunction "I/O14_37") (pintype "passive"))
    )
    (net (code "51") (name "/FSMC_D15") (class "Default")
      (node (ref "LCD") (pin "21") (pinfunction "DB15_21") (pintype "passive"))
      (node (ref "P2") (pin "6") (pinfunction "6_6") (pintype "passive"))
      (node (ref "U1") (pin "79") (pinfunction "PD10/FSMC_D15/U3_CK_79") (pintype "passive"))
      (node (ref "U3") (pin "38") (pinfunction "I/O15_38") (pintype "passive"))
    )
    (net (code "52") (name "/FSMC_NBL0") (class "Default")
      (node (ref "P2") (pin "56") (pinfunction "56_56") (pintype "passive"))
      (node (ref "U1") (pin "141") (pinfunction "PE0/TIM4_ETR/FSMC_NBL0/DCMI_D2_141") (pintype "passive"))
      (node (ref "U3") (pin "39") (pinfunction "LB_39") (pintype "passive"))
    )
    (net (code "53") (name "/FSMC_NBL1") (class "Default")
      (node (ref "P2") (pin "55") (pinfunction "55_55") (pintype "passive"))
      (node (ref "U1") (pin "142") (pinfunction "PE1/FSMC_NBL1/DCMI_D3_142") (pintype "passive"))
      (node (ref "U3") (pin "40") (pinfunction "UB_40") (pintype "passive"))
    )
    (net (code "54") (name "/FSMC_NE3") (class "Default")
      (node (ref "P2") (pin "41") (pinfunction "41_41") (pintype "passive"))
      (node (ref "R4") (pin "1") (pinfunction "1_1") (pintype "passive"))
      (node (ref "U1") (pin "125") (pinfunction "PG10/FSMC_NCE4_1/FSMC_NE3_125") (pintype "passive"))
      (node (ref "U3") (pin "6") (pinfunction "CE_6") (pintype "passive"))
    )
    (net (code "55") (name "/FSMC_NE4") (class "Default")
      (node (ref "LCD") (pin "1") (pinfunction "CS_1") (pintype "passive"))
      (node (ref "P2") (pin "43") (pinfunction "43_43") (pintype "passive"))
      (node (ref "U1") (pin "127") (pinfunction "PG12/FSMC_NE4/U6_RTS_127") (pintype "passive"))
    )
    (net (code "56") (name "/FSMC_NOE") (class "Default")
      (node (ref "LCD") (pin "4") (pinfunction "RD_4") (pintype "passive"))
      (node (ref "P2") (pin "38") (pinfunction "38_38") (pintype "passive"))
      (node (ref "U1") (pin "118") (pinfunction "PD4/FSMC_NOE/U2_RTS_118") (pintype "passive"))
      (node (ref "U3") (pin "41") (pinfunction "OE_41") (pintype "passive"))
    )
    (net (code "57") (name "/FSMC_NWE") (class "Default")
      (node (ref "LCD") (pin "3") (pinfunction "WR_3") (pintype "passive"))
      (node (ref "P2") (pin "37") (pinfunction "37_37") (pintype "passive"))
      (node (ref "U1") (pin "119") (pinfunction "PD5/FSMC_NWE/U2_TX_119") (pintype "passive"))
      (node (ref "U3") (pin "17") (pinfunction "WE_17") (pintype "passive"))
    )
    (net (code "58") (name "/F_CS") (class "Default")
      (node (ref "P2") (pin "2") (pinfunction "2_2") (pintype "passive"))
      (node (ref "U1") (pin "75") (pinfunction "PB14/SPI2_MISO/TIM1_CH2N/TIM8_CH2N/TIM12_CH1/U3_RTS/OTG_HS_DM/I2S2ext_SD_75") (pintype "passive"))
      (node (ref "U6") (pin "1") (pinfunction "CS_1") (pintype "passive"))
    )
    (net (code "59") (name "/IIC_SCL") (class "Default")
      (node (ref "P2") (pin "54") (pinfunction "54_54") (pintype "passive"))
      (node (ref "R11") (pin "1") (pinfunction "1_1") (pintype "passive"))
      (node (ref "U1") (pin "139") (pinfunction "PB8/TIM4_CH3/TIM10_CH1/CAN1_RX/SDIO_D4/ETH_MII_TXD3/I2C1_SCL/DCMI_D6_139") (pintype "passive"))
      (node (ref "U5") (pin "6") (pinfunction "SCL_6") (pintype "passive"))
    )
    (net (code "60") (name "/IIC_SDA") (class "Default")
      (node (ref "P2") (pin "53") (pinfunction "53_53") (pintype "passive"))
      (node (ref "R12") (pin "1") (pinfunction "1_1") (pintype "passive"))
      (node (ref "U1") (pin "140") (pinfunction "PB9/TIM4_CH4/TIM11_CH1/CAN1_TX/SDIO_D5/SPI2_NSS/I2C1_SDA/DCMI_D7/I2S2_WS_140") (pintype "passive"))
      (node (ref "U5") (pin "5") (pinfunction "SDA_5") (pintype "passive"))
    )
    (net (code "61") (name "/IO0") (class "Default")
      (node (ref "R30") (pin "1") (pinfunction "1_1") (pintype "passive"))
      (node (ref "TP5") (pin "1") (pinfunction "1_1") (pintype "passive"))
      (node (ref "U8") (pin "15") (pinfunction "GPIO0_15") (pintype "power_in"))
    )
    (net (code "62") (name "/IO2") (class "Default")
      (node (ref "DS4") (pin "2") (pinfunction "K_2") (pintype "passive"))
      (node (ref "TP6") (pin "1") (pinfunction "1_1") (pintype "passive"))
      (node (ref "U8") (pin "14") (pinfunction "GPIO2/U1TXD_14") (pintype "power_in"))
    )
    (net (code "63") (name "/IO4") (class "Default")
      (node (ref "U8") (pin "16") (pinfunction "GPIO4_16") (pintype "power_in"))
    )
    (net (code "64") (name "/IO5") (class "Default")
      (node (ref "U8") (pin "24") (pinfunction "GPIO5_24") (pintype "power_in"))
    )
    (net (code "65") (name "/IO9") (class "Default")
      (node (ref "U7") (pin "7") (pinfunction "~{HOLD}/O3_7") (pintype "power_in"))
      (node (ref "U8") (pin "18") (pinfunction "GPIO9/SD_DATA_2_18") (pintype "power_in"))
    )
    (net (code "66") (name "/IO10") (class "Default")
      (node (ref "U7") (pin "3") (pinfunction "~{WP}/IO2_3") (pintype "power_in"))
      (node (ref "U8") (pin "19") (pinfunction "GPIO10/SD_DATA_3_19") (pintype "power_in"))
    )
    (net (code "67") (name "/IO12") (class "Default")
      (node (ref "U8") (pin "10") (pinfunction "GPIO12/MTDI_10") (pintype "power_in"))
    )
    (net (code "68") (name "/IO13") (class "Default")
      (node (ref "U8") (pin "12") (pinfunction "GPIO13/MTCK/U2RXD_12") (pintype "power_in"))
    )
    (net (code "69") (name "/IO14") (class "Default")
      (node (ref "U8") (pin "9") (pinfunction "GPIO14/MTMS_9") (pintype "power_in"))
    )
    (net (code "70") (name "/IO15") (class "Default")
      (node (ref "R33") (pin "1") (pinfunction "1_1") (pintype "passive"))
      (node (ref "U8") (pin "13") (pinfunction "GPIO15/MTD0/U2TXD_13") (pintype "power_in"))
    )
    (net (code "71") (name "/IO16") (class "Default")
      (node (ref "U8") (pin "8") (pinfunction "GPIO16/XPD_DCDC_8") (pintype "power_in"))
    )
    (net (code "72") (name "/JTCK") (class "Default")
      (node (ref "J1") (pin "9") (pinfunction "TCK/SWCLK_9") (pintype "passive"))
      (node (ref "P2") (pin "27") (pinfunction "27_27") (pintype "passive"))
      (node (ref "R8") (pin "2") (pinfunction "2_2") (pintype "passive"))
      (node (ref "U1") (pin "109") (pinfunction "PA14/JTCK_SWCLK_109") (pintype "passive"))
    )
    (net (code "73") (name "/JTDI") (class "Default")
      (node (ref "J1") (pin "5") (pinfunction "TDI_5") (pintype "passive"))
      (node (ref "P2") (pin "30") (pinfunction "30_30") (pintype "passive"))
      (node (ref "R6") (pin "2") (pinfunction "2_2") (pintype "passive"))
      (node (ref "U1") (pin "110") (pinfunction "PA15/JTDI/SPI1_NSS/SPI3_NSS/TIM2_CH1_ETR/I2S3_WS_110") (pintype "passive"))
    )
    (net (code "74") (name "/JTDO") (class "Default")
      (node (ref "J1") (pin "15") (pinfunction "RESET#_15") (pintype "passive"))
      (node (ref "P2") (pin "47") (pinfunction "47_47") (pintype "passive"))
      (node (ref "R9") (pin "2") (pinfunction "2_2") (pintype "passive"))
      (node (ref "U1") (pin "133") (pinfunction "PB3/JTDO/TRACESWO/TIM2_CH2/SPI1_SCK/SPI3_SCK/I2S3_CK_133") (pintype "passive"))
      (node (ref "U6") (pin "6") (pinfunction "CLK_6") (pintype "passive"))
    )
    (net (code "75") (name "/JTMS") (class "Default")
      (node (ref "J1") (pin "7") (pinfunction "TMS/SWDIO_7") (pintype "passive"))
      (node (ref "P2") (pin "28") (pinfunction "28_28") (pintype "passive"))
      (node (ref "R7") (pin "2") (pinfunction "2_2") (pintype "passive"))
      (node (ref "U1") (pin "105") (pinfunction "PA13/JTMS_SWDIO_105") (pintype "passive"))
    )
    (net (code "76") (name "/JTRST") (class "Default")
      (node (ref "J1") (pin "3") (pinfunction "TRST_3") (pintype "passive"))
      (node (ref "P2") (pin "50") (pinfunction "50_50") (pintype "passive"))
      (node (ref "R5") (pin "2") (pinfunction "2_2") (pintype "passive"))
      (node (ref "U1") (pin "134") (pinfunction "PB4/JNTRST/TIM3_CH1/SPI1_MISO/SPI3_MISO/I2S3ext_SD_134") (pintype "passive"))
      (node (ref "U6") (pin "2") (pinfunction "SO_2") (pintype "passive"))
    )
    (net (code "77") (name "/KEY1") (class "Default")
      (node (ref "P1") (pin "33") (pinfunction "33_33") (pintype "passive"))
      (node (ref "S2") (pin "2") (pinfunction "2_2") (pintype "passive"))
      (node (ref "U1") (pin "34") (pinfunction "PA0-WKUP/U2_CTS/U4_TX/ETH_MII_CRS/TIM2_CH1_ETR/TIM5_CH1/TIM8_ETR/ADC123_IN0_34") (pintype "passive"))
    )
    (net (code "78") (name "/KEY2") (class "Default")
      (node (ref "P1") (pin "55") (pinfunction "55_55") (pintype "passive"))
      (node (ref "S3") (pin "2") (pinfunction "2_2") (pintype "passive"))
      (node (ref "U1") (pin "2") (pinfunction "PE3/TRACED0/FSMC_A19_2") (pintype "passive"))
    )
    (net (code "79") (name "/LCD_BL") (class "Default")
      (node (ref "LCD") (pin "23") (pinfunction "BL_23") (pintype "passive"))
      (node (ref "P2") (pin "1") (pinfunction "1_1") (pintype "passive"))
      (node (ref "U1") (pin "76") (pinfunction "PB15/SPI2_MOSI/TIM1_CH3N/TIM8_CH3N/TIM12_CH2/OTG_HS_DP/I2S2_SD_76") (pintype "passive"))
    )
    (net (code "80") (name "/LED1") (class "Default")
      (node (ref "DS2") (pin "2") (pinfunction "K_2") (pintype "passive"))
      (node (ref "P1") (pin "39") (pinfunction "39_39") (pintype "passive"))
      (node (ref "U1") (pin "21") (pinfunction "PF9/TIM14_CH1/FSMC_CD/ADC3_IN7_21") (pintype "passive"))
    )
    (net (code "81") (name "/LED2") (class "Default")
      (node (ref "DS3") (pin "2") (pinfunction "K_2") (pintype "passive"))
      (node (ref "P1") (pin "38") (pinfunction "38_38") (pintype "passive"))
      (node (ref "U1") (pin "22") (pinfunction "PF10/FSMC_INTR/ADC3_IN8_22") (pintype "passive"))
    )
    (net (code "82") (name "/PA5") (class "Default")
      (node (ref "P1") (pin "28") (pinfunction "28_28") (pintype "passive"))
      (node (ref "U1") (pin "41") (pinfunction "PA5/SPI1_SCK/OTG_HS_ULPI_CK/TIM2_CH1_ETR/TIM8_CH1N/DAC2_OUT/ADC12_IN5_41") (pintype "passive"))
    )
    (net (code "83") (name "/PA6") (class "Default")
      (node (ref "P1") (pin "27") (pinfunction "27_27") (pintype "passive"))
      (node (ref "U1") (pin "42") (pinfunction "PA6/SPI1_MISO/TIM1_BKIN/TIM3_CH1/TIM8_BKIN/TIM13_CH1/DCMI_PIXCLK/ADC12_IN6_42") (pintype "passive"))
    )
    (net (code "84") (name "/PA7") (class "Default")
      (node (ref "P1") (pin "26") (pinfunction "26_26") (pintype "passive"))
      (node (ref "U1") (pin "43") (pinfunction "PA7/SPI1_MOSI/TIM1_CH1N/TIM3_CH2/TIM8_CH1N/TIM14_CH1/ETH_MII_RX_DV/ETH_RMII_CRS_DV/ADC12_IN7_43") (pintype "passive"))
    )
    (net (code "85") (name "/PA8") (class "Default")
      (node (ref "P2") (pin "21") (pinfunction "21_21") (pintype "passive"))
      (node (ref "U1") (pin "100") (pinfunction "PA8/TIM1_CH1/U1_CK/I2C3_SCL/MCO1/OTG_FS_SOF_100") (pintype "passive"))
    )
    (net (code "86") (name "/PA11") (class "Default")
      (node (ref "P2") (pin "26") (pinfunction "26_26") (pintype "passive"))
      (node (ref "R2") (pin "2") (pinfunction "2_2") (pintype "passive"))
      (node (ref "U1") (pin "103") (pinfunction "PA11/TIM1_CH4/U1_CTS/CAN1_RX/OTG_FS_DM_103") (pintype "passive"))
    )
    (net (code "87") (name "/PA12") (class "Default")
      (node (ref "P2") (pin "25") (pinfunction "25_25") (pintype "passive"))
      (node (ref "R3") (pin "2") (pinfunction "2_2") (pintype "passive"))
      (node (ref "U1") (pin "104") (pinfunction "PA12/TIM1_ETR/U1_RTS/CAN1_TX/OTG_FS_DP_104") (pintype "passive"))
    )
    (net (code "88") (name "/PB0") (class "Default")
      (node (ref "LCD") (pin "34") (pinfunction "CLK_34") (pintype "passive"))
      (node (ref "P1") (pin "23") (pinfunction "23_23") (pintype "passive"))
      (node (ref "U1") (pin "46") (pinfunction "PB0/TIM1_CH2N/TIM3_CH3/TIM8_CH2N/OTG_HS_ULPI_D1/ETH_MII_RXD2/ADC12_IN8_46") (pintype "passive"))
    )
    (net (code "89") (name "/PB1") (class "Default")
      (node (ref "LCD") (pin "31") (pinfunction "T_PEN_31") (pintype "passive"))
      (node (ref "P1") (pin "22") (pinfunction "22_22") (pintype "passive"))
      (node (ref "U1") (pin "47") (pinfunction "PB1/TIM1_CH3N/TIM3_CH4/TIM8_CH3N/OTG_HS_INTN/ETH_MII_RXD3/ADC12_IN9_47") (pintype "passive"))
    )
    (net (code "90") (name "/PB5") (class "Default")
      (node (ref "P2") (pin "49") (pinfunction "49_49") (pintype "passive"))
      (node (ref "U1") (pin "135") (pinfunction "PB5/TIM3_CH2/SPI1_MOSI/SPI3_MOSI/CAN2_RX/I2C1_SMBA/OTG_HS_ULPI_D7/ETH_PPS_OUT/DCMI_D10/I2S3_SD_135") (pintype "passive"))
      (node (ref "U6") (pin "5") (pinfunction "SI_5") (pintype "passive"))
    )
    (net (code "91") (name "/PB6") (class "Default")
      (node (ref "P2") (pin "52") (pinfunction "52_52") (pintype "passive"))
      (node (ref "U1") (pin "136") (pinfunction "PB6/TIM4_CH1/U1_TX/CAN2_TX/I2C1_SCL/DCMI_D5_136") (pintype "passive"))
    )
    (net (code "92") (name "/PB7") (class "Default")
      (node (ref "P2") (pin "51") (pinfunction "51_51") (pintype "passive"))
      (node (ref "U1") (pin "137") (pinfunction "PB7/TIM4_CH2/U1_RX/FSMC_NL/I2C1_SDA/DCMI_VSYNC_137") (pintype "passive"))
    )
    (net (code "93") (name "/PB10") (class "Default")
      (node (ref "P1") (pin "4") (pinfunction "4_4") (pintype "passive"))
      (node (ref "U1") (pin "69") (pinfunction "PB10/SPI2_SCK/TIM2_CH3/U3_TX/I2C2_SCL/OTG_HS_ULPI_D3/I2S2_CK_69") (pintype "passive"))
    )
    (net (code "94") (name "/PB11") (class "Default")
      (node (ref "P1") (pin "3") (pinfunction "3_3") (pintype "passive"))
      (node (ref "U1") (pin "70") (pinfunction "PB11/TIM2_CH4/U3_RX/I2C2_SDA/HS_ULPI_D4/ETH_MII_TX_EN/ETH_RMII_TX_EN_70") (pintype "passive"))
    )
    (net (code "95") (name "/PB12") (class "Default")
      (node (ref "P1") (pin "2") (pinfunction "2_2") (pintype "passive"))
      (node (ref "U1") (pin "73") (pinfunction "PB12/SPI2_NSS/TIM1_BKIN/U3_CK/CAN2_RX/I2C2_SMBA/OTG_HS_ULPI_D5/OTG_HS_ID/ETH_MII_TXD0/ETH_RMII_TXD0/I2S2_WS_73") (pintype "passive"))
    )
    (net (code "96") (name "/PB13") (class "Default")
      (node (ref "P1") (pin "1") (pinfunction "1_1") (pintype "passive"))
      (node (ref "U1") (pin "74") (pinfunction "PB13/SPI2_SCK/TIM1_CH1N/U3_CTS/CAN2_TX/OTG_HS_ULPI_D6/OTG_HS_VBUS/ETH_MII_TXD1/ETH_RMII_TXD1/I2S2_CK_74") (pintype "passive"))
    )
    (net (code "97") (name "/PC0") (class "Default")
      (node (ref "P1") (pin "37") (pinfunction "37_37") (pintype "passive"))
      (node (ref "U1") (pin "26") (pinfunction "PC0/OTG_HS_ULPI_STP/ADC123_IN10_26") (pintype "passive"))
    )
    (net (code "98") (name "/PC1") (class "Default")
      (node (ref "P1") (pin "36") (pinfunction "36_36") (pintype "passive"))
      (node (ref "U1") (pin "27") (pinfunction "PC1/ETH_MDC/ADC123_IN11_27") (pintype "passive"))
    )
    (net (code "99") (name "/PC2") (class "Default")
      (node (ref "P1") (pin "35") (pinfunction "35_35") (pintype "passive"))
      (node (ref "U1") (pin "28") (pinfunction "PC2/SPI2_MISO/OTG_HS_ULPI_DIR/ETH_MII_TXD2/I2S2ext_SD/ADC123_IN12_28") (pintype "passive"))
    )
    (net (code "100") (name "/PC3") (class "Default")
      (node (ref "P1") (pin "34") (pinfunction "34_34") (pintype "passive"))
      (node (ref "U1") (pin "29") (pinfunction "PC3/SPI2_MOSI/OTG_HS_ULPI_NXT/ETH_MII_TX_CLK/I2S2_SD/ADC123_IN13_29") (pintype "passive"))
    )
    (net (code "101") (name "/PC4") (class "Default")
      (node (ref "P1") (pin "25") (pinfunction "25_25") (pintype "passive"))
      (node (ref "U1") (pin "44") (pinfunction "PC4/ETH_MII_RXD0/ETH_RMII_RXD0/ADC12_IN14_44") (pintype "passive"))
    )
    (net (code "102") (name "/PC5") (class "Default")
      (node (ref "P1") (pin "24") (pinfunction "24_24") (pintype "passive"))
      (node (ref "U1") (pin "45") (pinfunction "PC5/ETH_MII_RXD1/ETH_RMII_RXD1/ADC12_IN15_45") (pintype "passive"))
    )
    (net (code "103") (name "/PC6") (class "Default")
      (node (ref "P2") (pin "17") (pinfunction "17_17") (pintype "passive"))
      (node (ref "U1") (pin "96") (pinfunction "PC6/TIM3_CH1/TIM8_CH1/U6_TX/SDIO_D6/DCMI_D0/I2S2_MCK_96") (pintype "passive"))
    )
    (net (code "104") (name "/PC7") (class "Default")
      (node (ref "P2") (pin "20") (pinfunction "20_20") (pintype "passive"))
      (node (ref "U1") (pin "97") (pinfunction "PC7/TIM3_CH2/TIM8_CH2/U6_RX/SDIO_D7/DCMI_D1/I2S3_MCK_97") (pintype "passive"))
    )
    (net (code "105") (name "/PC8") (class "Default")
      (node (ref "J2") (pin "7") (pinfunction "DAT0_7") (pintype "passive"))
      (node (ref "P2") (pin "19") (pinfunction "19_19") (pintype "passive"))
      (node (ref "R19") (pin "2") (pinfunction "2_2") (pintype "passive"))
      (node (ref "U1") (pin "98") (pinfunction "PC8/TIM3_CH3/TIM8_CH3/U6_CK/SDIO_D0/DCMI_D2_98") (pintype "passive"))
    )
    (net (code "106") (name "/PC9") (class "Default")
      (node (ref "J2") (pin "8") (pinfunction "DAT1_8") (pintype "passive"))
      (node (ref "P2") (pin "22") (pinfunction "22_22") (pintype "passive"))
      (node (ref "R20") (pin "2") (pinfunction "2_2") (pintype "passive"))
      (node (ref "U1") (pin "99") (pinfunction "PC9/TIM3_CH4/TIM8_CH4/I2C3_SDA/SDIO_D1/DCMI_D3/MCO2/I2S_CKIN_99") (pintype "passive"))
    )
    (net (code "107") (name "/PC10") (class "Default")
      (node (ref "J2") (pin "1") (pinfunction "DAT2_1") (pintype "passive"))
      (node (ref "P2") (pin "29") (pinfunction "29_29") (pintype "passive"))
      (node (ref "R15") (pin "2") (pinfunction "2_2") (pintype "passive"))
      (node (ref "U1") (pin "111") (pinfunction "PC10/SPI3_SCK/U3_TX/U4_TX/SDIO_D2/DCMI_D8/I2S3_CK_111") (pintype "passive"))
    )
    (net (code "108") (name "/PC11") (class "Default")
      (node (ref "J2") (pin "2") (pinfunction "CD/DAT3_2") (pintype "passive"))
      (node (ref "P2") (pin "32") (pinfunction "32_32") (pintype "passive"))
      (node (ref "R16") (pin "2") (pinfunction "2_2") (pintype "passive"))
      (node (ref "U1") (pin "112") (pinfunction "PC11/SPI3_MISO/U3_RX/U4_RX/SDIO_D3/DCMI_D4/I2S3ext_SD_112") (pintype "passive"))
    )
    (net (code "109") (name "/PC12") (class "Default")
      (node (ref "J2") (pin "5") (pinfunction "CLK_5") (pintype "passive"))
      (node (ref "P2") (pin "31") (pinfunction "31_31") (pintype "passive"))
      (node (ref "U1") (pin "113") (pinfunction "PC12/SPI3_MOSI/U3_CK/U5_TX/SDIO_CK/DCMI_D9/I2S3_SD_113") (pintype "passive"))
    )
    (net (code "110") (name "/PC13") (class "Default")
      (node (ref "LCD") (pin "33") (pinfunction "T_CS_33") (pintype "passive"))
      (node (ref "P1") (pin "51") (pinfunction "51_51") (pintype "passive"))
      (node (ref "U1") (pin "7") (pinfunction "PC13/RTC_AF1_7") (pintype "passive"))
    )
    (net (code "111") (name "/PC14") (class "Default")
      (node (ref "C14") (pin "1") (pinfunction "1_1") (pintype "passive"))
      (node (ref "P1") (pin "50") (pinfunction "50_50") (pintype "passive"))
      (node (ref "U1") (pin "8") (pinfunction "PC14-OSC32_IN_8") (pintype "passive"))
      (node (ref "Y2") (pin "2") (pinfunction "OSC2_2") (pintype "passive"))
    )
    (net (code "112") (name "/PC15") (class "Default")
      (node (ref "C15") (pin "1") (pinfunction "1_1") (pintype "passive"))
      (node (ref "P1") (pin "49") (pinfunction "49_49") (pintype "passive"))
      (node (ref "U1") (pin "9") (pinfunction "PC15-OSC32_OUT_9") (pintype "passive"))
      (node (ref "Y2") (pin "1") (pinfunction "OSC1_1") (pintype "passive"))
    )
    (net (code "113") (name "/PD2") (class "Default")
      (node (ref "J2") (pin "3") (pinfunction "CMD_3") (pintype "passive"))
      (node (ref "P2") (pin "36") (pinfunction "36_36") (pintype "passive"))
      (node (ref "R18") (pin "2") (pinfunction "2_2") (pintype "passive"))
      (node (ref "U1") (pin "116") (pinfunction "PD2/TIM3_ETR/U5_RX/SDIO_CMD/DCMI_D11_116") (pintype "passive"))
    )
    (net (code "114") (name "/PD3") (class "Default")
      (node (ref "P2") (pin "35") (pinfunction "35_35") (pintype "passive"))
      (node (ref "U1") (pin "117") (pinfunction "PD3/FSMC_CLK/U2_CTS_117") (pintype "passive"))
    )
    (net (code "115") (name "/PD6") (class "Default")
      (node (ref "P2") (pin "40") (pinfunction "40_40") (pintype "passive"))
      (node (ref "U1") (pin "122") (pinfunction "PD6/FSMC_NWAIT/U2_RX_122") (pintype "passive"))
    )
    (net (code "116") (name "/PD7") (class "Default")
      (node (ref "P2") (pin "39") (pinfunction "39_39") (pintype "passive"))
      (node (ref "U1") (pin "123") (pinfunction "PD7/FSMC_NE1/FSMC_NCE2/U2_CK_123") (pintype "passive"))
    )
    (net (code "117") (name "/PE2") (class "Default")
      (node (ref "P1") (pin "56") (pinfunction "56_56") (pintype "passive"))
      (node (ref "U1") (pin "1") (pinfunction "PE2/TRACECLK/FSMC_A23/ETH_MII_TXD3_1") (pintype "passive"))
    )
    (net (code "118") (name "/PE4") (class "Default")
      (node (ref "P1") (pin "54") (pinfunction "54_54") (pintype "passive"))
      (node (ref "U1") (pin "3") (pinfunction "PE4/TRACED1/FSMC_A20/DCMI_D4_3") (pintype "passive"))
    )
    (net (code "119") (name "/PE5") (class "Default")
      (node (ref "P1") (pin "53") (pinfunction "53_53") (pintype "passive"))
      (node (ref "U1") (pin "4") (pinfunction "PE5/TRACED2/FSMC_A21/TIM9_CH1/DCMI_D6_4") (pintype "passive"))
    )
    (net (code "120") (name "/PE6") (class "Default")
      (node (ref "P1") (pin "52") (pinfunction "52_52") (pintype "passive"))
      (node (ref "U1") (pin "5") (pinfunction "PE6/TRACED3/FSMC_A22/TIM9_CH2/DCMI_D7_5") (pintype "passive"))
    )
    (net (code "121") (name "/PF6") (class "Default")
      (node (ref "P1") (pin "42") (pinfunction "42_42") (pintype "passive"))
      (node (ref "U1") (pin "18") (pinfunction "PF6/TIM10_CH1/FSMC_NIORD/ADC3_IN4_18") (pintype "passive"))
    )
    (net (code "122") (name "/PF7") (class "Default")
      (node (ref "P1") (pin "41") (pinfunction "41_41") (pintype "passive"))
      (node (ref "U1") (pin "19") (pinfunction "PF7/TIM11_CH1/FSMC_NREG/ADC3_IN5_19") (pintype "passive"))
    )
    (net (code "123") (name "/PF8") (class "Default")
      (node (ref "P1") (pin "40") (pinfunction "40_40") (pintype "passive"))
      (node (ref "U1") (pin "20") (pinfunction "PF8/TIM13_CH1/FSMC_NIOWR/ADC3_IN6_20") (pintype "passive"))
    )
    (net (code "124") (name "/PF11") (class "Default")
      (node (ref "LCD") (pin "30") (pinfunction "MOSI_30") (pintype "passive"))
      (node (ref "P1") (pin "20") (pinfunction "20_20") (pintype "passive"))
      (node (ref "U1") (pin "49") (pinfunction "PF11/DCMI_D12_49") (pintype "passive"))
    )
    (net (code "125") (name "/PG6") (class "Default")
      (node (ref "P2") (pin "16") (pinfunction "16_16") (pintype "passive"))
      (node (ref "U1") (pin "91") (pinfunction "PG6/FSMC_INT2_91") (pintype "passive"))
    )
    (net (code "126") (name "/PG7") (class "Default")
      (node (ref "P2") (pin "15") (pinfunction "15_15") (pintype "passive"))
      (node (ref "U1") (pin "92") (pinfunction "PG7/FSMC_INT3/U6_CK_92") (pintype "passive"))
    )
    (net (code "127") (name "/PG8") (class "Default")
      (node (ref "P2") (pin "18") (pinfunction "18_18") (pintype "passive"))
      (node (ref "U1") (pin "93") (pinfunction "PG8/U6_RTS/ETH_PPS_OUT_93") (pintype "passive"))
    )
    (net (code "128") (name "/PG9") (class "Default")
      (node (ref "P2") (pin "42") (pinfunction "42_42") (pintype "passive"))
      (node (ref "U1") (pin "124") (pinfunction "PG9/FSMC_NE2/FSMC_NCE3/U6_RX_124") (pintype "passive"))
    )
    (net (code "129") (name "/PG11") (class "Default")
      (node (ref "P2") (pin "44") (pinfunction "44_44") (pintype "passive"))
      (node (ref "U1") (pin "126") (pinfunction "PG11/FSMC_NCE4_2/ETH_MII_TX_EN/ETH_RMII_TX_EN_126") (pintype "passive"))
    )
    (net (code "130") (name "/PG13") (class "Default")
      (node (ref "P2") (pin "46") (pinfunction "46_46") (pintype "passive"))
      (node (ref "U1") (pin "128") (pinfunction "PG13/FSMC_A24/U6_CTS/ETH_MII_TXD0/ETH_RMII_TXD0_128") (pintype "passive"))
    )
    (net (code "131") (name "/PG14") (class "Default")
      (node (ref "P2") (pin "45") (pinfunction "45_45") (pintype "passive"))
      (node (ref "U1") (pin "129") (pinfunction "PG14/FSMC_A25/U6_TX/ETH_MII_TXD1/ETH_RMII_TXD1_129") (pintype "passive"))
    )
    (net (code "132") (name "/PG15") (class "Default")
      (node (ref "P2") (pin "48") (pinfunction "48_48") (pintype "passive"))
      (node (ref "U1") (pin "132") (pinfunction "PG15/U6_CTS/DCMI_D13_132") (pintype "passive"))
    )
    (net (code "133") (name "/RESET") (class "Default")
      (node (ref "C37") (pin "2") (pinfunction "2_2") (pintype "passive"))
      (node (ref "J1") (pin "17") (pinfunction "NC_17") (pintype "passive"))
      (node (ref "LCD") (pin "5") (pinfunction "RST_5") (pintype "passive"))
      (node (ref "R21") (pin "1") (pinfunction "1_1") (pintype "passive"))
      (node (ref "S1") (pin "1") (pinfunction "1_1") (pintype "passive"))
      (node (ref "U1") (pin "25") (pinfunction "NRST_25") (pintype "passive"))
    )
    (net (code "134") (name "/VBAT") (class "Default")
      (node (ref "C46") (pin "1") (pinfunction "1_1") (pintype "passive"))
      (node (ref "D1") (pin "2") (pintype "passive"))
      (node (ref "D2") (pin "2") (pintype "passive"))
      (node (ref "U1") (pin "6") (pinfunction "VBAT_6") (pintype "passive"))
    )
    (net (code "135") (name "/VREF+") (class "Default")
      (node (ref "U1") (pin "32") (pinfunction "Vref+_32") (pintype "passive"))
    )
    (net (code "136") (name "GND") (class "Default")
      (node (ref "BT1") (pin "2") (pinfunction "GND_2") (pintype "passive"))
      (node (ref "C1") (pin "2") (pinfunction "GND_2") (pintype "passive"))
      (node (ref "C10") (pin "2") (pinfunction "2_2") (pintype "passive"))
      (node (ref "C11") (pin "2") (pinfunction "2_2") (pintype "passive"))
      (node (ref "C12") (pin "2") (pinfunction "2_2") (pintype "passive"))
      (node (ref "C13") (pin "2") (pinfunction "2_2") (pintype "passive"))
      (node (ref "C14") (pin "2") (pinfunction "2_2") (pintype "passive"))
      (node (ref "C15") (pin "2") (pinfunction "2_2") (pintype "passive"))
      (node (ref "C16") (pin "2") (pinfunction "2_2") (pintype "passive"))
      (node (ref "C17") (pin "2") (pinfunction "2_2") (pintype "passive"))
      (node (ref "C18") (pin "1") (pinfunction "1_1") (pintype "passive"))
      (node (ref "C19") (pin "2") (pinfunction "2_2") (pintype "passive"))
      (node (ref "C2") (pin "1") (pinfunction "1_1") (pintype "passive"))
      (node (ref "C20") (pin "1") (pinfunction "1_1") (pintype "passive"))
      (node (ref "C21") (pin "1") (pinfunction "1_1") (pintype "passive"))
      (node (ref "C22") (pin "1") (pinfunction "1_1") (pintype "passive"))
      (node (ref "C23") (pin "1") (pinfunction "1_1") (pintype "passive"))
      (node (ref "C24") (pin "2") (pinfunction "2_2") (pintype "passive"))
      (node (ref "C25") (pin "1") (pinfunction "1_1") (pintype "passive"))
      (node (ref "C26") (pin "1") (pinfunction "1_1") (pintype "passive"))
      (node (ref "C27") (pin "1") (pinfunction "1_1") (pintype "passive"))
      (node (ref "C28") (pin "1") (pinfunction "1_1") (pintype "passive"))
      (node (ref "C29") (pin "1") (pinfunction "1_1") (pintype "passive"))
      (node (ref "C3") (pin "1") (pinfunction "1_1") (pintype "passive"))
      (node (ref "C30") (pin "1") (pinfunction "1_1") (pintype "passive"))
      (node (ref "C31") (pin "1") (pinfunction "1_1") (pintype "passive"))
      (node (ref "C32") (pin "1") (pinfunction "1_1") (pintype "passive"))
      (node (ref "C33") (pin "1") (pinfunction "1_1") (pintype "passive"))
      (node (ref "C34") (pin "1") (pinfunction "1_1") (pintype "passive"))
      (node (ref "C35") (pin "1") (pinfunction "1_1") (pintype "passive"))
      (node (ref "C36") (pin "1") (pinfunction "1_1") (pintype "passive"))
      (node (ref "C37") (pin "1") (pinfunction "1_1") (pintype "passive"))
      (node (ref "C38") (pin "1") (pinfunction "1_1") (pintype "passive"))
      (node (ref "C39") (pin "1") (pinfunction "1_1") (pintype "passive"))
      (node (ref "C4") (pin "1") (pinfunction "1_1") (pintype "passive"))
      (node (ref "C40") (pin "1") (pinfunction "1_1") (pintype "passive"))
      (node (ref "C41") (pin "1") (pinfunction "1_1") (pintype "passive"))
      (node (ref "C43") (pin "2") (pinfunction "2_2") (pintype "passive"))
      (node (ref "C44") (pin "1") (pinfunction "1_1") (pintype "passive"))
      (node (ref "C45") (pin "1") (pinfunction "1_1") (pintype "passive"))
      (node (ref "C46") (pin "2") (pinfunction "2_2") (pintype "passive"))
      (node (ref "C5") (pin "1") (pinfunction "1_1") (pintype "passive"))
      (node (ref "C6") (pin "1") (pinfunction "1_1") (pintype "passive"))
      (node (ref "C7") (pin "2") (pinfunction "2_2") (pintype "passive"))
      (node (ref "C8") (pin "2") (pinfunction "2_2") (pintype "passive"))
      (node (ref "C9") (pin "2") (pinfunction "2_2") (pintype "passive"))
      (node (ref "DS1") (pin "2") (pinfunction "K_2") (pintype "passive"))
      (node (ref "E1") (pin "2") (pinfunction "2_2") (pintype "power_in"))
      (node (ref "FB1") (pin "2") (pintype "passive"))
      (node (ref "J1") (pin "10") (pinfunction "GND_10") (pintype "passive"))
      (node (ref "J1") (pin "12") (pinfunction "GND_12") (pintype "passive"))
      (node (ref "J1") (pin "14") (pinfunction "GND_14") (pintype "passive"))
      (node (ref "J1") (pin "16") (pinfunction "GND_16") (pintype "passive"))
      (node (ref "J1") (pin "18") (pinfunction "GND_18") (pintype "passive"))
      (node (ref "J1") (pin "20") (pinfunction "GND_20") (pintype "passive"))
      (node (ref "J1") (pin "4") (pinfunction "GND_4") (pintype "passive"))
      (node (ref "J1") (pin "6") (pinfunction "GND_6") (pintype "passive"))
      (node (ref "J1") (pin "8") (pinfunction "GND_8") (pintype "passive"))
      (node (ref "J2") (pin "10") (pinfunction "SW1_10") (pintype "passive"))
      (node (ref "J2") (pin "11") (pinfunction "11_11") (pintype "passive"))
      (node (ref "J2") (pin "12") (pinfunction "12_12") (pintype "passive"))
      (node (ref "J2") (pin "13") (pinfunction "13_13") (pintype "passive"))
      (node (ref "J2") (pin "6") (pinfunction "VSS_6") (pintype "passive"))
      (node (ref "J2") (pin "9") (pinfunction "SW2_9") (pintype "passive"))
      (node (ref "J3") (pin "5") (pinfunction "5_5") (pintype "passive"))
      (node (ref "J3") (pin "6") (pinfunction "6_6") (pintype "passive"))
      (node (ref "LCD") (pin "22") (pinfunction "GND_22") (pintype "passive"))
      (node (ref "LCD") (pin "26") (pinfunction "GND_26") (pintype "passive"))
      (node (ref "LCD") (pin "27") (pinfunction "GND_27") (pintype "passive"))
      (node (ref "P1") (pin "57") (pinfunction "57_57") (pintype "passive"))
      (node (ref "P1") (pin "59") (pinfunction "59_59") (pintype "passive"))
      (node (ref "P2") (pin "57") (pinfunction "57_57") (pintype "passive"))
      (node (ref "P2") (pin "59") (pinfunction "59_59") (pintype "passive"))
      (node (ref "R14") (pin "2") (pinfunction "2_2") (pintype "passive"))
      (node (ref "R32") (pin "2") (pinfunction "2_2") (pintype "passive"))
      (node (ref "R33") (pin "2") (pinfunction "2_2") (pintype "passive"))
      (node (ref "R8") (pin "1") (pinfunction "1_1") (pintype "passive"))
      (node (ref "S1") (pin "2") (pinfunction "2_2") (pintype "passive"))
      (node (ref "S3") (pin "1") (pinfunction "1_1") (pintype "passive"))
      (node (ref "U1") (pin "107") (pinfunction "VSS_107") (pintype "passive"))
      (node (ref "U1") (pin "120") (pinfunction "VSS_120") (pintype "passive"))
      (node (ref "U1") (pin "130") (pinfunction "VSS_130") (pintype "passive"))
      (node (ref "U1") (pin "16") (pinfunction "VSS_16") (pintype "passive"))
      (node (ref "U1") (pin "31") (pinfunction "VSSA_31") (pintype "passive"))
      (node (ref "U1") (pin "38") (pinfunction "VSS_38") (pintype "passive"))
      (node (ref "U1") (pin "51") (pinfunction "VSS_51") (pintype "passive"))
      (node (ref "U1") (pin "61") (pinfunction "VSS_61") (pintype "passive"))
      (node (ref "U1") (pin "83") (pinfunction "VSS_83") (pintype "passive"))
      (node (ref "U1") (pin "94") (pinfunction "VSS_94") (pintype "passive"))
      (node (ref "U2") (pin "1") (pinfunction "GND_1") (pintype "passive"))
      (node (ref "U3") (pin "12") (pinfunction "GND_12") (pintype "passive"))
      (node (ref "U3") (pin "34") (pinfunction "GND_34") (pintype "passive"))
      (node (ref "U4") (pin "1") (pinfunction "GND_1") (pintype "passive"))
      (node (ref "U5") (pin "1") (pinfunction "A0_1") (pintype "passive"))
      (node (ref "U5") (pin "2") (pinfunction "A1_2") (pintype "passive"))
      (node (ref "U5") (pin "3") (pinfunction "A2_3") (pintype "passive"))
      (node (ref "U5") (pin "4") (pinfunction "GND_4") (pintype "passive"))
      (node (ref "U5") (pin "7") (pinfunction "WP_7") (pintype "passive"))
      (node (ref "U6") (pin "4") (pinfunction "GND_4") (pintype "passive"))
      (node (ref "U7") (pin "4") (pinfunction "GND_4") (pintype "power_in"))
      (node (ref "U8") (pin "33") (pinfunction "GND_33") (pintype "power_in"))
      (node (ref "USB_SLAVE1") (pin "5") (pinfunction "GND_5") (pintype "passive"))
      (node (ref "USB_SLAVE2") (pin "5") (pinfunction "GND_5") (pintype "passive"))
      (node (ref "Y4") (pin "2") (pinfunction "2_2") (pintype "passive"))
      (node (ref "Y4") (pin "4") (pinfunction "4_4") (pintype "passive"))
    )
    (net (code "137") (name "Net-(BT1-VCC)") (class "Default")
      (node (ref "BT1") (pin "1") (pinfunction "VCC_1") (pintype "passive"))
      (node (ref "D2") (pin "1") (pintype "passive"))
    )
    (net (code "138") (name "Net-(DS1-A)") (class "Default")
      (node (ref "DS1") (pin "1") (pinfunction "A_1") (pintype "passive"))
      (node (ref "R1") (pin "2") (pinfunction "2_2") (pintype "passive"))
    )
    (net (code "139") (name "Net-(DS2-A)") (class "Default")
      (node (ref "DS2") (pin "1") (pinfunction "A_1") (pintype "passive"))
      (node (ref "R27") (pin "2") (pinfunction "2_2") (pintype "passive"))
    )
    (net (code "140") (name "Net-(DS3-A)") (class "Default")
      (node (ref "DS3") (pin "1") (pinfunction "A_1") (pintype "passive"))
      (node (ref "R28") (pin "2") (pinfunction "2_2") (pintype "passive"))
    )
    (net (code "141") (name "Net-(DS4-A)") (class "Default")
      (node (ref "DS4") (pin "1") (pinfunction "A_1") (pintype "passive"))
      (node (ref "R31") (pin "1") (pinfunction "1_1") (pintype "passive"))
    )
    (net (code "142") (name "Net-(F1-Pad1)") (class "Default")
      (node (ref "F1") (pin "1") (pinfunction "1_1") (pintype "passive"))
      (node (ref "SW1") (pin "2") (pinfunction "2_2") (pintype "passive"))
    )
    (net (code "143") (name "Net-(J3-Pad3)") (class "Default")
      (node (ref "J3") (pin "3") (pinfunction "3_3") (pintype "passive"))
      (node (ref "R23") (pin "2") (pinfunction "2_2") (pintype "passive"))
    )
    (net (code "144") (name "Net-(J3-Pad4)") (class "Default")
      (node (ref "J3") (pin "4") (pinfunction "4_4") (pintype "passive"))
      (node (ref "R24") (pin "1") (pinfunction "1_1") (pintype "passive"))
    )
    (net (code "145") (name "Net-(U1-PDR_ON)") (class "Default")
      (node (ref "R14") (pin "1") (pinfunction "1_1") (pintype "passive"))
      (node (ref "R17") (pin "1") (pinfunction "1_1") (pintype "passive"))
      (node (ref "U1") (pin "143") (pinfunction "PDR_ON_143") (pintype "passive"))
    )
    (net (code "146") (name "Net-(U1-PH0-OSC_IN)") (class "Default")
      (node (ref "C17") (pin "1") (pinfunction "1_1") (pintype "passive"))
      (node (ref "R10") (pin "2") (pinfunction "2_2") (pintype "passive"))
      (node (ref "U1") (pin "23") (pinfunction "PH0-OSC_IN_23") (pintype "passive"))
      (node (ref "Y3") (pin "2") (pinfunction "OSC2_2") (pintype "passive"))
    )
    (net (code "147") (name "Net-(U1-PH1-OSC_OUT)") (class "Default")
      (node (ref "C16") (pin "1") (pinfunction "1_1") (pintype "passive"))
      (node (ref "R10") (pin "1") (pinfunction "1_1") (pintype "passive"))
      (node (ref "U1") (pin "24") (pinfunction "PH1-OSC_OUT_24") (pintype "passive"))
      (node (ref "Y3") (pin "1") (pinfunction "OSC1_1") (pintype "passive"))
    )
    (net (code "148") (name "Net-(U1-VDDA)") (class "Default")
      (node (ref "C21") (pin "2") (pinfunction "2_2") (pintype "passive"))
      (node (ref "C22") (pin "2") (pinfunction "2_2") (pintype "passive"))
      (node (ref "R13") (pin "1") (pinfunction "1_1") (pintype "passive"))
      (node (ref "U1") (pin "33") (pinfunction "VDDA_33") (pintype "passive"))
    )
    (net (code "149") (name "Net-(U1-Vcap_1)") (class "Default")
      (node (ref "C18") (pin "2") (pinfunction "2_2") (pintype "passive"))
      (node (ref "U1") (pin "71") (pinfunction "Vcap_1_71") (pintype "passive"))
    )
    (net (code "150") (name "Net-(U1-Vcap_2)") (class "Default")
      (node (ref "C20") (pin "2") (pinfunction "2_2") (pintype "passive"))
      (node (ref "U1") (pin "106") (pinfunction "Vcap_2_106") (pintype "passive"))
    )
    (net (code "151") (name "Net-(U4-V3)") (class "Default")
      (node (ref "C7") (pin "1") (pinfunction "1_1") (pintype "passive"))
      (node (ref "U4") (pin "4") (pinfunction "V3_4") (pintype "passive"))
    )
    (net (code "152") (name "Net-(U4-XI)") (class "Default")
      (node (ref "C11") (pin "1") (pinfunction "1_1") (pintype "passive"))
      (node (ref "U4") (pin "7") (pinfunction "XI_7") (pintype "passive"))
      (node (ref "Y1") (pin "2") (pinfunction "OSC2_2") (pintype "passive"))
    )
    (net (code "153") (name "Net-(U4-XO)") (class "Default")
      (node (ref "C10") (pin "1") (pinfunction "1_1") (pintype "passive"))
      (node (ref "U4") (pin "8") (pinfunction "XO_8") (pintype "passive"))
      (node (ref "Y1") (pin "1") (pinfunction "OSC1_1") (pintype "passive"))
    )
    (net (code "154") (name "Net-(U8-LAN)") (class "Default")
      (node (ref "C42") (pin "2") (pinfunction "2_2") (pintype "passive"))
      (node (ref "FB1") (pin "1") (pintype "passive"))
      (node (ref "U8") (pin "2") (pinfunction "LAN_2") (pintype "power_in"))
    )
    (net (code "155") (name "Net-(U8-RES12K)") (class "Default")
      (node (ref "R32") (pin "1") (pinfunction "1_1") (pintype "passive"))
      (node (ref "U8") (pin "31") (pinfunction "RES12K_31") (pintype "power_in"))
    )
    (net (code "156") (name "Net-(U8-XTAL_IN)") (class "Default")
      (node (ref "C45") (pin "2") (pinfunction "2_2") (pintype "passive"))
      (node (ref "U8") (pin "28") (pinfunction "XTAL_IN_28") (pintype "power_in"))
      (node (ref "Y4") (pin "3") (pinfunction "3_3") (pintype "passive"))
    )
    (net (code "157") (name "Net-(U8-XTAL_OUT)") (class "Default")
      (node (ref "C44") (pin "2") (pinfunction "2_2") (pintype "passive"))
      (node (ref "U8") (pin "27") (pinfunction "XTAL_OUT_27") (pintype "power_in"))
      (node (ref "Y4") (pin "1") (pinfunction "1_1") (pintype "passive"))
    )
    (net (code "158") (name "Net-(USB_SLAVE2-D+)") (class "Default")
      (node (ref "R3") (pin "1") (pinfunction "1_1") (pintype "passive"))
      (node (ref "USB_SLAVE2") (pin "3") (pinfunction "D+_3") (pintype "passive"))
    )
    (net (code "159") (name "Net-(USB_SLAVE2-D-)") (class "Default")
      (node (ref "R2") (pin "1") (pinfunction "1_1") (pintype "passive"))
      (node (ref "USB_SLAVE2") (pin "2") (pinfunction "D-_2") (pintype "passive"))
    )
    (net (code "160") (name "VCC3.3") (class "Default")
      (node (ref "C12") (pin "1") (pinfunction "1_1") (pintype "passive"))
      (node (ref "C19") (pin "1") (pinfunction "1_1") (pintype "passive"))
      (node (ref "C23") (pin "2") (pinfunction "2_2") (pintype "passive"))
      (node (ref "C24") (pin "1") (pinfunction "1_1") (pintype "passive"))
      (node (ref "C3") (pin "2") (pinfunction "2_2") (pintype "passive"))
      (node (ref "C39") (pin "2") (pinfunction "2_2") (pintype "passive"))
      (node (ref "C4") (pin "2") (pinfunction "2_2") (pintype "passive"))
      (node (ref "C40") (pin "2") (pinfunction "2_2") (pintype "passive"))
      (node (ref "C41") (pin "2") (pinfunction "2_2") (pintype "passive"))
      (node (ref "C8") (pin "1") (pinfunction "1_1") (pintype "passive"))
      (node (ref "C9") (pin "1") (pinfunction "1_1") (pintype "passive"))
      (node (ref "J1") (pin "1") (pinfunction "VDD_1") (pintype "passive"))
      (node (ref "J1") (pin "2") (pinfunction "VDD_2") (pintype "passive"))
      (node (ref "J2") (pin "4") (pinfunction "VDD_4") (pintype "passive"))
      (node (ref "J3") (pin "1") (pinfunction "1_1") (pintype "passive"))
      (node (ref "J3") (pin "2") (pinfunction "2_2") (pintype "passive"))
      (node (ref "LCD") (pin "24") (pinfunction "VDD3.3_24") (pintype "passive"))
      (node (ref "LCD") (pin "25") (pinfunction "VDD3.3_25") (pintype "passive"))
      (node (ref "P1") (pin "58") (pinfunction "58_58") (pintype "passive"))
      (node (ref "P1") (pin "60") (pinfunction "60_60") (pintype "passive"))
      (node (ref "R1") (pin "1") (pinfunction "1_1") (pintype "passive"))
      (node (ref "R11") (pin "2") (pinfunction "2_2") (pintype "passive"))
      (node (ref "R12") (pin "2") (pinfunction "2_2") (pintype "passive"))
      (node (ref "R13") (pin "2") (pinfunction "2_2") (pintype "passive"))
      (node (ref "R15") (pin "1") (pinfunction "1_1") (pintype "passive"))
      (node (ref "R16") (pin "1") (pinfunction "1_1") (pintype "passive"))
      (node (ref "R18") (pin "1") (pinfunction "1_1") (pintype "passive"))
      (node (ref "R19") (pin "1") (pinfunction "1_1") (pintype "passive"))
      (node (ref "R20") (pin "1") (pinfunction "1_1") (pintype "passive"))
      (node (ref "R21") (pin "2") (pinfunction "2_2") (pintype "passive"))
      (node (ref "R22") (pin "2") (pinfunction "2_2") (pintype "passive"))
      (node (ref "R25") (pin "2") (pinfunction "2_2") (pintype "passive"))
      (node (ref "R26") (pin "2") (pinfunction "2_2") (pintype "passive"))
      (node (ref "R27") (pin "1") (pinfunction "1_1") (pintype "passive"))
      (node (ref "R28") (pin "1") (pinfunction "1_1") (pintype "passive"))
      (node (ref "R29") (pin "2") (pinfunction "2_2") (pintype "passive"))
      (node (ref "R30") (pin "2") (pinfunction "2_2") (pintype "passive"))
      (node (ref "R31") (pin "2") (pinfunction "2_2") (pintype "passive"))
      (node (ref "R5") (pin "1") (pinfunction "1_1") (pintype "passive"))
      (node (ref "R6") (pin "1") (pinfunction "1_1") (pintype "passive"))
      (node (ref "R7") (pin "1") (pinfunction "1_1") (pintype "passive"))
      (node (ref "R9") (pin "1") (pinfunction "1_1") (pintype "passive"))
      (node (ref "S2") (pin "1") (pinfunction "1_1") (pintype "passive"))
      (node (ref "U2") (pin "2") (pinfunction "OUT_2") (pintype "passive"))
      (node (ref "U2") (pin "4") (pinfunction "OUT_4") (pintype "passive"))
      (node (ref "U3") (pin "11") (pinfunction "VDD_11") (pintype "passive"))
      (node (ref "U3") (pin "33") (pinfunction "VDD_33") (pintype "passive"))
      (node (ref "U5") (pin "8") (pinfunction "VCC1_8") (pintype "passive"))
      (node (ref "U6") (pin "3") (pinfunction "WP#_3") (pintype "passive"))
      (node (ref "U6") (pin "7") (pinfunction "HOLD_7") (pintype "passive"))
      (node (ref "U6") (pin "8") (pinfunction "VCC_8") (pintype "passive"))
      (node (ref "U7") (pin "8") (pinfunction "VCC_8") (pintype "power_in"))
      (node (ref "U8") (pin "1") (pinfunction "VDDA_1") (pintype "power_in"))
      (node (ref "U8") (pin "11") (pinfunction "VDDPST_11") (pintype "power_in"))
      (node (ref "U8") (pin "17") (pinfunction "VDDPST_17") (pintype "power_in"))
      (node (ref "U8") (pin "29") (pinfunction "VDDD_29") (pintype "power_in"))
      (node (ref "U8") (pin "3") (pinfunction "VDD3P3_3") (pintype "power_in"))
      (node (ref "U8") (pin "30") (pinfunction "VDDA_30") (pintype "power_in"))
      (node (ref "U8") (pin "4") (pinfunction "VDD3P3_4") (pintype "power_in"))
    )
    (net (code "161") (name "VCC3.3M") (class "Default")
      (node (ref "C25") (pin "2") (pinfunction "2_2") (pintype "passive"))
      (node (ref "C26") (pin "2") (pinfunction "2_2") (pintype "passive"))
      (node (ref "C27") (pin "2") (pinfunction "2_2") (pintype "passive"))
      (node (ref "C28") (pin "2") (pinfunction "2_2") (pintype "passive"))
      (node (ref "C29") (pin "2") (pinfunction "2_2") (pintype "passive"))
      (node (ref "C30") (pin "2") (pinfunction "2_2") (pintype "passive"))
      (node (ref "C31") (pin "2") (pinfunction "2_2") (pintype "passive"))
      (node (ref "C32") (pin "2") (pinfunction "2_2") (pintype "passive"))
      (node (ref "C33") (pin "2") (pinfunction "2_2") (pintype "passive"))
      (node (ref "C34") (pin "2") (pinfunction "2_2") (pintype "passive"))
      (node (ref "C35") (pin "2") (pinfunction "2_2") (pintype "passive"))
      (node (ref "C36") (pin "2") (pinfunction "2_2") (pintype "passive"))
      (node (ref "D1") (pin "1") (pintype "passive"))
      (node (ref "R17") (pin "2") (pinfunction "2_2") (pintype "passive"))
      (node (ref "R22") (pin "1") (pinfunction "1_1") (pintype "passive"))
      (node (ref "R25") (pin "1") (pinfunction "1_1") (pintype "passive"))
      (node (ref "R4") (pin "2") (pinfunction "2_2") (pintype "passive"))
      (node (ref "U1") (pin "108") (pinfunction "VDD_108") (pintype "passive"))
      (node (ref "U1") (pin "121") (pinfunction "VDD_121") (pintype "passive"))
      (node (ref "U1") (pin "131") (pinfunction "VDD_131") (pintype "passive"))
      (node (ref "U1") (pin "144") (pinfunction "VDD_144") (pintype "passive"))
      (node (ref "U1") (pin "17") (pinfunction "VDD_17") (pintype "passive"))
      (node (ref "U1") (pin "30") (pinfunction "VDD_30") (pintype "passive"))
      (node (ref "U1") (pin "39") (pinfunction "VDD_39") (pintype "passive"))
      (node (ref "U1") (pin "52") (pinfunction "VDD_52") (pintype "passive"))
      (node (ref "U1") (pin "62") (pinfunction "VDD_62") (pintype "passive"))
      (node (ref "U1") (pin "72") (pinfunction "VDD_72") (pintype "passive"))
      (node (ref "U1") (pin "84") (pinfunction "VDD_84") (pintype "passive"))
      (node (ref "U1") (pin "95") (pinfunction "VDD_95") (pintype "passive"))
    )
    (net (code "162") (name "VCC5") (class "Default")
      (node (ref "C1") (pin "1") (pinfunction "VCC_1") (pintype "passive"))
      (node (ref "C13") (pin "1") (pinfunction "1_1") (pintype "passive"))
      (node (ref "C2") (pin "2") (pinfunction "2_2") (pintype "passive"))
      (node (ref "C5") (pin "2") (pinfunction "2_2") (pintype "passive"))
      (node (ref "C6") (pin "2") (pinfunction "2_2") (pintype "passive"))
      (node (ref "F1") (pin "2") (pinfunction "2_2") (pintype "passive"))
      (node (ref "LCD") (pin "28") (pinfunction "BL_VDD_28") (pintype "passive"))
      (node (ref "P2") (pin "58") (pinfunction "58_58") (pintype "passive"))
      (node (ref "P2") (pin "60") (pinfunction "60_60") (pintype "passive"))
      (node (ref "U2") (pin "3") (pinfunction "IN_3") (pintype "passive"))
      (node (ref "U4") (pin "16") (pinfunction "VCC_16") (pintype "passive"))
    )
    (net (code "163") (name "VUSB") (class "Default")
      (node (ref "SW1") (pin "1") (pinfunction "1_1") (pintype "passive"))
      (node (ref "USB_SLAVE1") (pin "1") (pinfunction "VCC_1") (pintype "passive"))
      (node (ref "USB_SLAVE2") (pin "1") (pinfunction "VCC_1") (pintype "passive"))
    )
    (net (code "164") (name "unconnected-(J1-NC-Pad11)") (class "Default")
      (node (ref "J1") (pin "11") (pinfunction "NC_11") (pintype "passive"))
    )
    (net (code "165") (name "unconnected-(J1-NC-Pad19)") (class "Default")
      (node (ref "J1") (pin "19") (pinfunction "NC_19") (pintype "passive"))
    )
    (net (code "166") (name "unconnected-(J1-TDO{slash}SWO-Pad13)") (class "Default")
      (node (ref "J1") (pin "13") (pinfunction "TDO/SWO_13") (pintype "passive"))
    )
    (net (code "167") (name "unconnected-(LCD-MO-Pad32)") (class "Default")
      (node (ref "LCD") (pin "32") (pinfunction "MO_32") (pintype "passive+no_connect"))
    )
    (net (code "168") (name "unconnected-(SW1-Pad3)") (class "Default")
      (node (ref "SW1") (pin "3") (pinfunction "3_3") (pintype "passive"))
    )
    (net (code "169") (name "unconnected-(U4-CTS#-Pad9)") (class "Default")
      (node (ref "U4") (pin "9") (pinfunction "CTS#_9") (pintype "passive"))
    )
    (net (code "170") (name "unconnected-(U4-DCD#-Pad12)") (class "Default")
      (node (ref "U4") (pin "12") (pinfunction "DCD#_12") (pintype "passive"))
    )
    (net (code "171") (name "unconnected-(U4-DSR#-Pad10)") (class "Default")
      (node (ref "U4") (pin "10") (pinfunction "DSR#_10") (pintype "passive"))
    )
    (net (code "172") (name "unconnected-(U4-DTR#-Pad13)") (class "Default")
      (node (ref "U4") (pin "13") (pinfunction "DTR#_13") (pintype "passive"))
    )
    (net (code "173") (name "unconnected-(U4-R232-Pad15)") (class "Default")
      (node (ref "U4") (pin "15") (pinfunction "R232_15") (pintype "passive"))
    )
    (net (code "174") (name "unconnected-(U4-RI#-Pad11)") (class "Default")
      (node (ref "U4") (pin "11") (pinfunction "RI#_11") (pintype "passive"))
    )
    (net (code "175") (name "unconnected-(U4-RTS#-Pad14)") (class "Default")
      (node (ref "U4") (pin "14") (pinfunction "RTS#_14") (pintype "passive"))
    )
    (net (code "176") (name "unconnected-(U8-VDD_RTC-Pad5)") (class "Default")
      (node (ref "U8") (pin "5") (pinfunction "VDD_RTC_5") (pintype "power_in+no_connect"))
    )
    (net (code "177") (name "unconnected-(USB_SLAVE1-NC-Pad4)") (class "Default")
      (node (ref "USB_SLAVE1") (pin "4") (pinfunction "NC_4") (pintype "passive"))
    )
    (net (code "178") (name "unconnected-(USB_SLAVE2-NC-Pad4)") (class "Default")
      (node (ref "USB_SLAVE2") (pin "4") (pinfunction "NC_4") (pintype "passive"))
    )
  )
)
